# Schem_Motherboard.net
KiCad netlist of a schematic drawn in Altium Designer
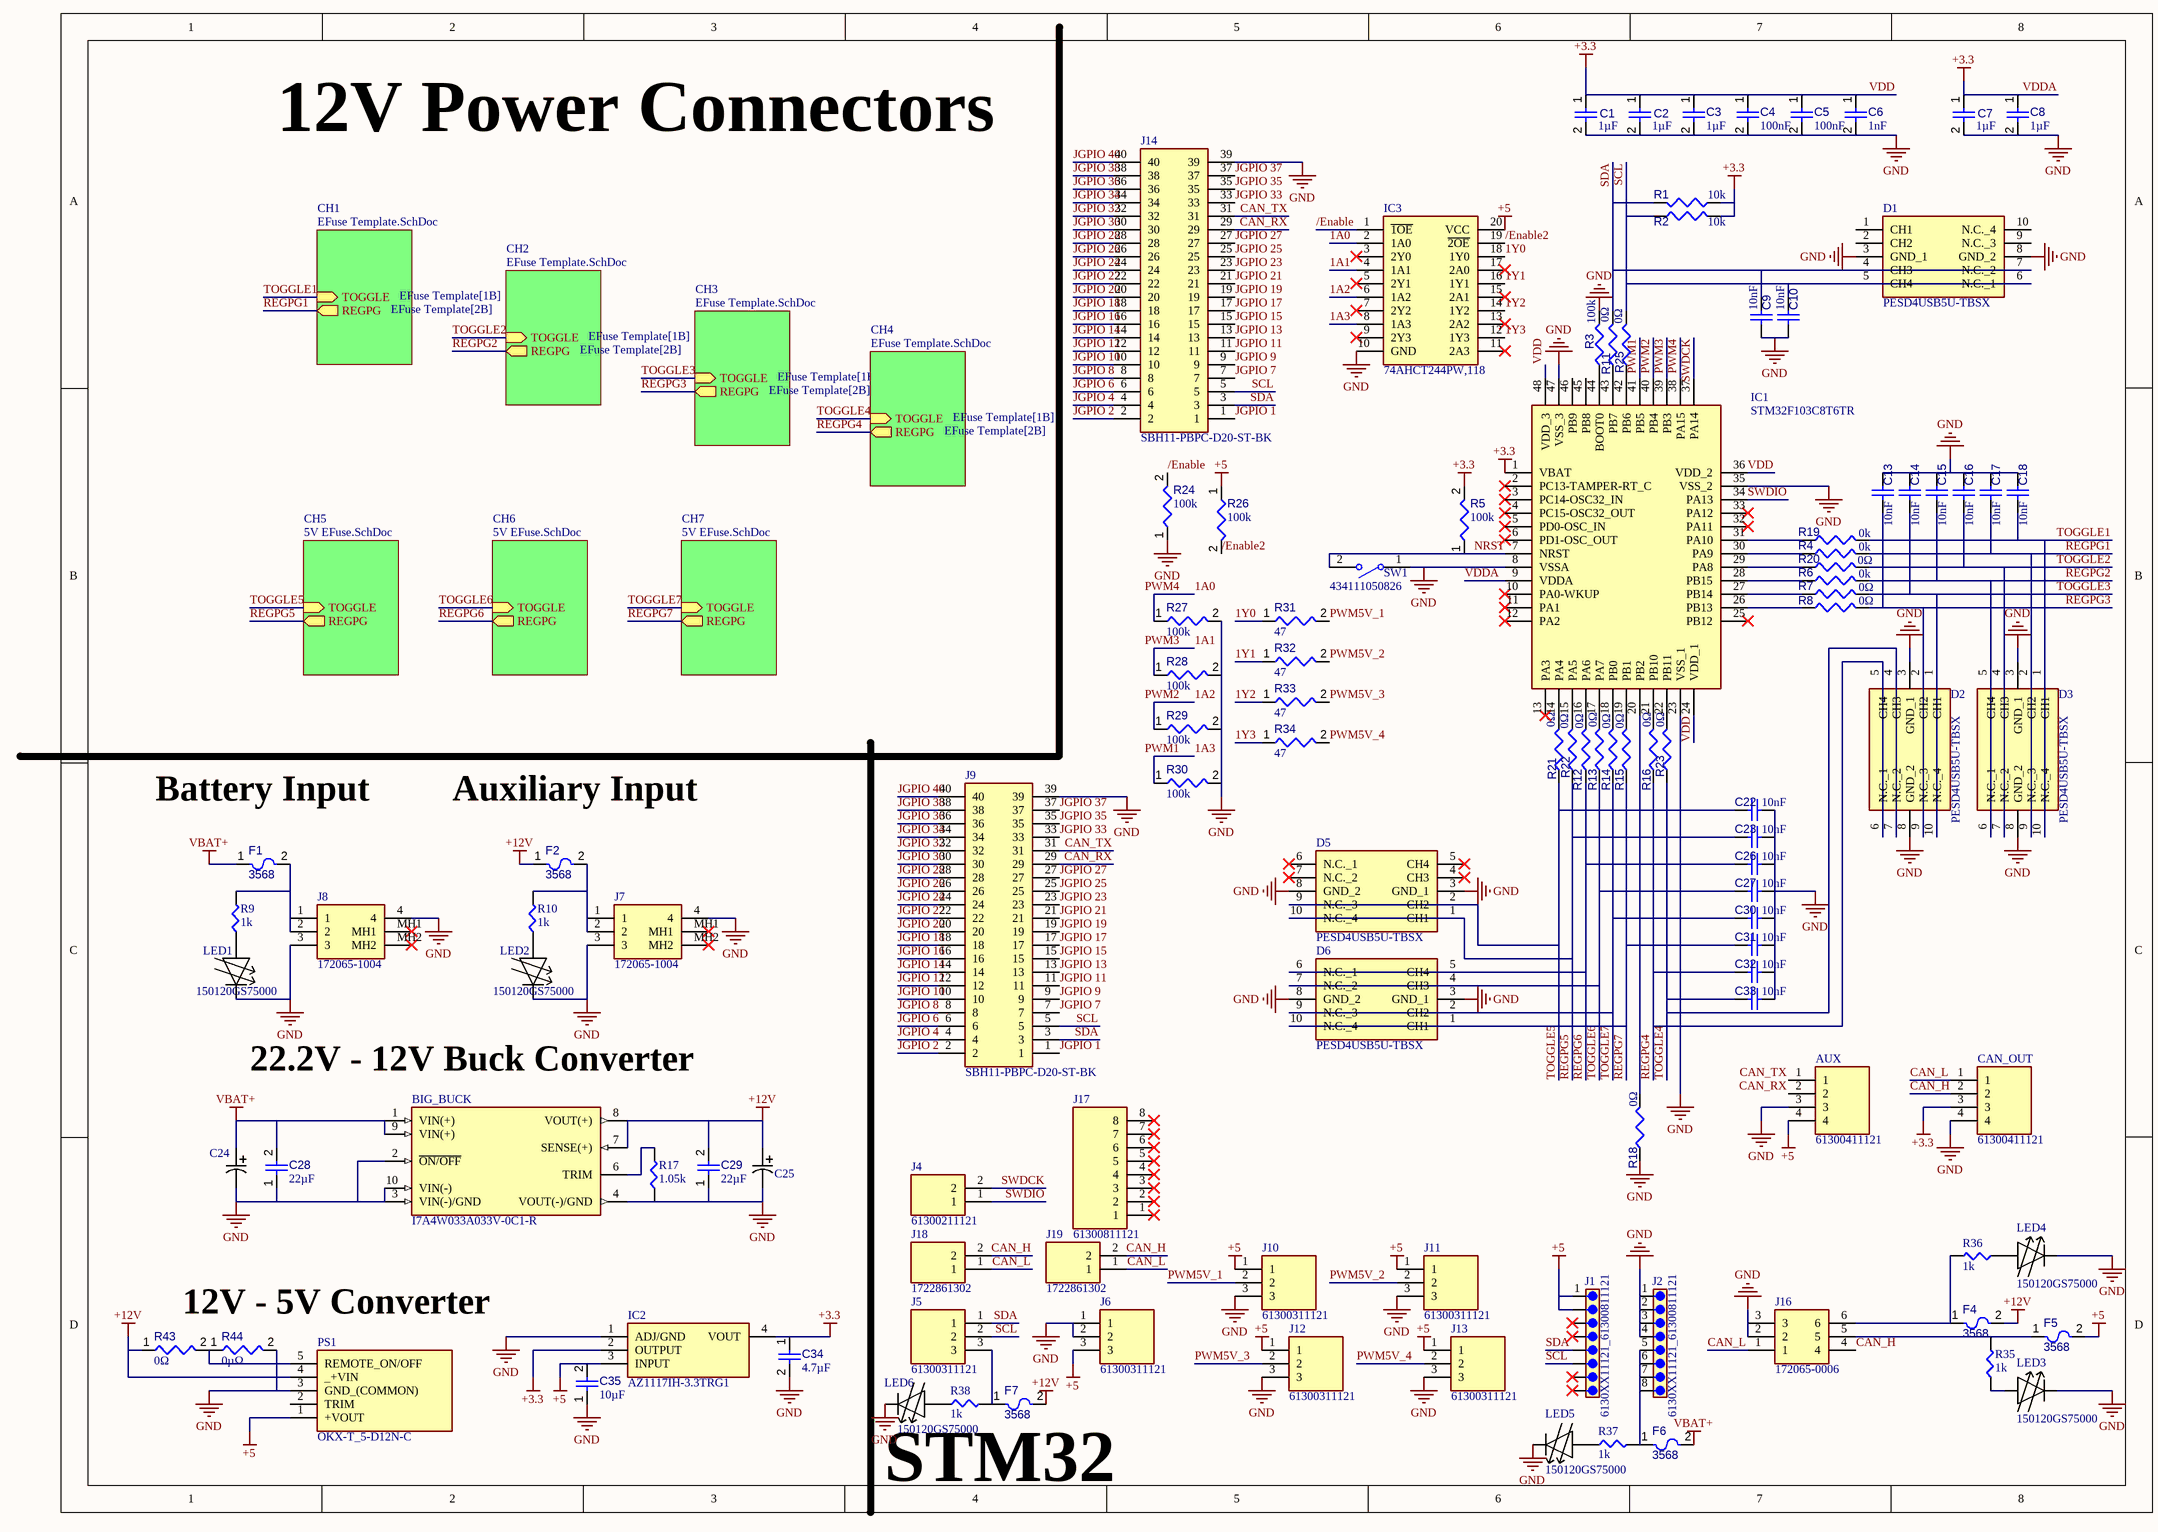
[diagram p0: Schem Motherboard.SchDoc]

(export (version "E")
  (design (tool "Eeschema 10.0.6"))
  (components
    (comp (ref "AUX")
      (value "61300411121")
      (footprint "SamacSys:HDRV4W95P0X254_1X4_1016X254X854P")
      (description "Connector")
      (fields (field (name "MOUSER PART NUMBER") "710-61300411121"))
      (libsource (lib "*") (part "61300411121"))
    )
    (comp (ref "BIG_BUCK")
      (value "I7A4W033A033V-0C1-R")
      (footprint "CONV_I7A4W033A033V-0C1-R")
      (description "Non-Isolated PoL Module DC DC Converter 1 Output 3.3V ~ 24V - - - 33A 18V - 60V Input")
      (fields (field (name "MF") "TDK-Lambda Americas Inc"))
      (libsource (lib "CPRT Workspace") (part "I7A4W033A033V-0C1-R"))
    )
    (comp (ref "C1")
      (value "1µF")
      (footprint "CAPC1608X94X35NL15T15")
      (description "Chip Capacitor, 1 uF, +/- 10%, 16 V, 0603 (1608 Metric)")
      (fields (field (name "TOLERANCE") "10%") (field (name "Comment") "Capacitor 1 uF +/- 10% 16 V 0603"))
      (libsource (lib "CPRT Workspace") (part "CAP-NP-2"))
    )
    (comp (ref "C2")
      (value "1µF")
      (footprint "CAPC1608X94X35NL15T15")
      (description "Chip Capacitor, 1 uF, +/- 10%, 16 V, 0603 (1608 Metric)")
      (fields (field (name "TOLERANCE") "10%") (field (name "Comment") "Capacitor 1 uF +/- 10% 16 V 0603"))
      (libsource (lib "CPRT Workspace") (part "CAP-NP-2"))
    )
    (comp (ref "C3")
      (value "1µF")
      (footprint "CAPC1608X94X35NL15T15")
      (description "Chip Capacitor, 1 uF, +/- 10%, 16 V, 0603 (1608 Metric)")
      (fields (field (name "TOLERANCE") "10%") (field (name "Comment") "Capacitor 1 uF +/- 10% 16 V 0603"))
      (libsource (lib "CPRT Workspace") (part "CAP-NP-2"))
    )
    (comp (ref "C4")
      (value "100nF")
      (footprint "CAPC1608X94X35NL15T15")
      (description "Chip Capacitor, 1 uF, +/- 10%, 16 V, 0603 (1608 Metric)")
      (fields (field (name "TOLERANCE") "10%") (field (name "Comment") "Capacitor 1 uF +/- 10% 16 V 0603"))
      (libsource (lib "CPRT Workspace") (part "CAP-NP-2"))
    )
    (comp (ref "C5")
      (value "100nF")
      (footprint "CAPC1608X94X35NL15T15")
      (description "Chip Capacitor, 1 uF, +/- 10%, 16 V, 0603 (1608 Metric)")
      (fields (field (name "TOLERANCE") "10%") (field (name "Comment") "Capacitor 1 uF +/- 10% 16 V 0603"))
      (libsource (lib "CPRT Workspace") (part "CAP-NP-2"))
    )
    (comp (ref "C6")
      (value "1nF")
      (footprint "CAPC1608X94X35NL15T15")
      (description "Chip Capacitor, 1 uF, +/- 10%, 16 V, 0603 (1608 Metric)")
      (fields (field (name "TOLERANCE") "10%") (field (name "Comment") "Capacitor 1 uF +/- 10% 16 V 0603"))
      (libsource (lib "CPRT Workspace") (part "CAP-NP-2"))
    )
    (comp (ref "C7")
      (value "1µF")
      (footprint "CAPC1608X94X35NL15T15")
      (description "Chip Capacitor, 1 uF, +/- 10%, 16 V, 0603 (1608 Metric)")
      (fields (field (name "TOLERANCE") "10%") (field (name "Comment") "Capacitor 1 uF +/- 10% 16 V 0603"))
      (libsource (lib "CPRT Workspace") (part "CAP-NP-2"))
    )
    (comp (ref "C8")
      (value "1µF")
      (footprint "CAPC1608X94X35NL15T15")
      (description "Chip Capacitor, 1 uF, +/- 10%, 16 V, 0603 (1608 Metric)")
      (fields (field (name "TOLERANCE") "10%") (field (name "Comment") "Capacitor 1 uF +/- 10% 16 V 0603"))
      (libsource (lib "CPRT Workspace") (part "CAP-NP-2"))
    )
    (comp (ref "C9")
      (value "10nF")
      (footprint "CAPC0402(1005)60_L")
      (description "Chip Capacitor, 10nF +/-20%, 50V, 0402, Thickness 0.6 mm")
      (fields (field (name "TOLERANCE") "5%") (field (name "Comment") "Capacitor 10nF +/-20% 50V 0402"))
      (libsource (lib "") (part "CAP-NP-2_1"))
    )
    (comp (ref "C10")
      (value "10nF")
      (footprint "CAPC0402(1005)60_L")
      (description "Chip Capacitor, 10nF +/-20%, 50V, 0402, Thickness 0.6 mm")
      (fields (field (name "TOLERANCE") "5%") (field (name "Comment") "Capacitor 10nF +/-20% 50V 0402"))
      (libsource (lib "") (part "CAP-NP-2_1"))
    )
    (comp (ref "C13")
      (value "10nF")
      (footprint "CAPC0402(1005)60_L")
      (description "Chip Capacitor, 10nF +/-20%, 50V, 0402, Thickness 0.6 mm")
      (fields (field (name "TOLERANCE") "5%") (field (name "Comment") "Capacitor 10nF +/-20% 50V 0402"))
      (libsource (lib "") (part "CAP-NP-2_1"))
    )
    (comp (ref "C14")
      (value "10nF")
      (footprint "CAPC0402(1005)60_L")
      (description "Chip Capacitor, 10nF +/-20%, 50V, 0402, Thickness 0.6 mm")
      (fields (field (name "TOLERANCE") "5%") (field (name "Comment") "Capacitor 10nF +/-20% 50V 0402"))
      (libsource (lib "") (part "CAP-NP-2_1"))
    )
    (comp (ref "C15")
      (value "10nF")
      (footprint "CAPC0402(1005)60_L")
      (description "Chip Capacitor, 10nF +/-20%, 50V, 0402, Thickness 0.6 mm")
      (fields (field (name "TOLERANCE") "5%") (field (name "Comment") "Capacitor 10nF +/-20% 50V 0402"))
      (libsource (lib "") (part "CAP-NP-2_1"))
    )
    (comp (ref "C16")
      (value "10nF")
      (footprint "CAPC0402(1005)60_L")
      (description "Chip Capacitor, 10nF +/-20%, 50V, 0402, Thickness 0.6 mm")
      (fields (field (name "TOLERANCE") "5%") (field (name "Comment") "Capacitor 10nF +/-20% 50V 0402"))
      (libsource (lib "") (part "CAP-NP-2_1"))
    )
    (comp (ref "C17")
      (value "10nF")
      (footprint "CAPC0402(1005)60_L")
      (description "Chip Capacitor, 10nF +/-20%, 50V, 0402, Thickness 0.6 mm")
      (fields (field (name "TOLERANCE") "5%") (field (name "Comment") "Capacitor 10nF +/-20% 50V 0402"))
      (libsource (lib "") (part "CAP-NP-2_1"))
    )
    (comp (ref "C18")
      (value "10nF")
      (footprint "CAPC0402(1005)60_L")
      (description "Chip Capacitor, 10nF +/-20%, 50V, 0402, Thickness 0.6 mm")
      (fields (field (name "TOLERANCE") "5%") (field (name "Comment") "Capacitor 10nF +/-20% 50V 0402"))
      (libsource (lib "") (part "CAP-NP-2_1"))
    )
    (comp (ref "C22")
      (value "10nF")
      (footprint "CAPC0402(1005)60_L")
      (description "Chip Capacitor, 10nF +/-20%, 50V, 0402, Thickness 0.6 mm")
      (fields (field (name "TOLERANCE") "5%") (field (name "Comment") "Capacitor 10nF +/-20% 50V 0402"))
      (libsource (lib "") (part "CAP-NP-2_1"))
    )
    (comp (ref "C23")
      (value "10nF")
      (footprint "CAPC0402(1005)60_L")
      (description "Chip Capacitor, 10nF +/-20%, 50V, 0402, Thickness 0.6 mm")
      (fields (field (name "TOLERANCE") "5%") (field (name "Comment") "Capacitor 10nF +/-20% 50V 0402"))
      (libsource (lib "") (part "CAP-NP-2_1"))
    )
    (comp (ref "C24")
      (value "UWT1E331MNL1GS")
      (footprint "PCAP_8x10-ELECT_NCA")
      (fields (field (name "COPYRIGHT") "Copyright (C) 2024 Ultra Librarian. All rights reserved."))
      (libsource (lib "CPRT Workspace") (part "UWT1E331MNL1GS"))
    )
    (comp (ref "C25")
      (value "UWT1E331MNL1GS")
      (footprint "PCAP_8x10-ELECT_NCA")
      (fields (field (name "COPYRIGHT") "Copyright (C) 2024 Ultra Librarian. All rights reserved."))
      (libsource (lib "CPRT Workspace") (part "UWT1E331MNL1GS"))
    )
    (comp (ref "C26")
      (value "10nF")
      (footprint "CAPC0402(1005)60_L")
      (description "Chip Capacitor, 10nF +/-20%, 50V, 0402, Thickness 0.6 mm")
      (fields (field (name "TOLERANCE") "5%") (field (name "Comment") "Capacitor 10nF +/-20% 50V 0402"))
      (libsource (lib "") (part "CAP-NP-2_1"))
    )
    (comp (ref "C27")
      (value "10nF")
      (footprint "CAPC0402(1005)60_L")
      (description "Chip Capacitor, 10nF +/-20%, 50V, 0402, Thickness 0.6 mm")
      (fields (field (name "TOLERANCE") "5%") (field (name "Comment") "Capacitor 10nF +/-20% 50V 0402"))
      (libsource (lib "") (part "CAP-NP-2_1"))
    )
    (comp (ref "C28")
      (value "22µF")
      (footprint "FP-GRM32E-0_3-0_2-IPC_C")
      (fields (field (name "Comment") "GRM32ER71E226ME15K"))
      (libsource (lib "CPRT Workspace") (part "CAP-NP-2"))
    )
    (comp (ref "C29")
      (value "22µF")
      (footprint "CAPC0805(2012)145_L")
      (description "Chip Capacitor, 22µF +/-40%, 16V, 0805, Thickness 1.45 mm")
      (fields (field (name "TOLERANCE") "5%") (field (name "Comment") "Capacitor 22µF +/-40% 16V 0805"))
      (libsource (lib "CPRT Workspace") (part "CAP-NP-2"))
    )
    (comp (ref "C30")
      (value "10nF")
      (footprint "CAPC0402(1005)60_L")
      (description "Chip Capacitor, 10nF +/-20%, 50V, 0402, Thickness 0.6 mm")
      (fields (field (name "TOLERANCE") "5%") (field (name "Comment") "Capacitor 10nF +/-20% 50V 0402"))
      (libsource (lib "") (part "CAP-NP-2_1"))
    )
    (comp (ref "C31")
      (value "10nF")
      (footprint "CAPC0402(1005)60_L")
      (description "Chip Capacitor, 10nF +/-20%, 50V, 0402, Thickness 0.6 mm")
      (fields (field (name "TOLERANCE") "5%") (field (name "Comment") "Capacitor 10nF +/-20% 50V 0402"))
      (libsource (lib "") (part "CAP-NP-2_1"))
    )
    (comp (ref "C32")
      (value "10nF")
      (footprint "CAPC0402(1005)60_L")
      (description "Chip Capacitor, 10nF +/-20%, 50V, 0402, Thickness 0.6 mm")
      (fields (field (name "TOLERANCE") "5%") (field (name "Comment") "Capacitor 10nF +/-20% 50V 0402"))
      (libsource (lib "") (part "CAP-NP-2_1"))
    )
    (comp (ref "C33")
      (value "10nF")
      (footprint "CAPC0402(1005)60_L")
      (description "Chip Capacitor, 10nF +/-20%, 50V, 0402, Thickness 0.6 mm")
      (fields (field (name "TOLERANCE") "5%") (field (name "Comment") "Capacitor 10nF +/-20% 50V 0402"))
      (libsource (lib "") (part "CAP-NP-2_1"))
    )
    (comp (ref "C34")
      (value "4.7µF")
      (footprint "CAPC0805(2012)145_L")
      (description "Chip Capacitor, 4.7µF +/-40%, 25V, 0805, Thickness 1.45 mm")
      (fields (field (name "TOLERANCE") "20%") (field (name "Comment") "Capacitor 4.7µF +/-40% 25V 0805"))
      (libsource (lib "CPRT Workspace") (part "CAP-NP-2"))
    )
    (comp (ref "C35")
      (value "10µF")
      (footprint "CAPC3216X180X50NL20T25")
      (description "Chip Capacitor, 10 uF, +/- 10%, 16 V, 1206 (3216 Metric)")
      (fields (field (name "TOLERANCE") "10%") (field (name "Comment") "Capacitor 10 uF +/- 10% 16 V 1206"))
      (libsource (lib "CPRT Workspace") (part "CAP-NP-2"))
    )
    (comp (ref "CAN_OUT")
      (value "61300411121")
      (footprint "SamacSys:HDRV4W95P0X254_1X4_1016X254X854P")
      (description "Connector")
      (fields (field (name "MOUSER PART NUMBER") "710-61300411121"))
      (libsource (lib "*") (part "61300411121"))
    )
    (comp (ref "D1")
      (value "PESD4USB5U-TBSX")
      (footprint "SamacSys:SON50P100X250X80-10N")
      (description "Diode")
      (fields (field (name "MOUSER PART NUMBER") "771-PESD4USB5U-TBSX"))
      (libsource (lib "*") (part "PESD4USB5U-TBSX"))
    )
    (comp (ref "D2")
      (value "PESD4USB5U-TBSX")
      (footprint "SamacSys:SON50P100X250X80-10N")
      (description "Diode")
      (fields (field (name "MOUSER PART NUMBER") "771-PESD4USB5U-TBSX"))
      (libsource (lib "") (part "PESD4USB5U-TBSX_1"))
    )
    (comp (ref "D3")
      (value "PESD4USB5U-TBSX")
      (footprint "SamacSys:SON50P100X250X80-10N")
      (description "Diode")
      (fields (field (name "MOUSER PART NUMBER") "771-PESD4USB5U-TBSX"))
      (libsource (lib "") (part "PESD4USB5U-TBSX_1"))
    )
    (comp (ref "D5")
      (value "PESD4USB5U-TBSX")
      (footprint "SamacSys:SON50P100X250X80-10N")
      (description "Diode")
      (fields (field (name "MOUSER PART NUMBER") "771-PESD4USB5U-TBSX"))
      (libsource (lib "") (part "PESD4USB5U-TBSX_2"))
    )
    (comp (ref "D6")
      (value "PESD4USB5U-TBSX")
      (footprint "SamacSys:SON50P100X250X80-10N")
      (description "Diode")
      (fields (field (name "MOUSER PART NUMBER") "771-PESD4USB5U-TBSX"))
      (libsource (lib "") (part "PESD4USB5U-TBSX_2"))
    )
    (comp (ref "F1")
      (value "3568")
      (footprint "KSTN-3568_V")
      (description "Fuses/Accessories")
      (libsource (lib "CPRT Workspace") (part "FUSE-2"))
    )
    (comp (ref "F2")
      (value "3568")
      (footprint "KSTN-3568_V")
      (description "Fuses/Accessories")
      (libsource (lib "CPRT Workspace") (part "FUSE-2"))
    )
    (comp (ref "F4")
      (value "3568")
      (footprint "KSTN-3568_V")
      (description "Fuses/Accessories")
      (libsource (lib "CPRT Workspace") (part "FUSE-2"))
    )
    (comp (ref "F5")
      (value "3568")
      (footprint "KSTN-3568_V")
      (description "Fuses/Accessories")
      (libsource (lib "CPRT Workspace") (part "FUSE-2"))
    )
    (comp (ref "F6")
      (value "3568")
      (footprint "KSTN-3568_V")
      (description "Fuses/Accessories")
      (libsource (lib "CPRT Workspace") (part "FUSE-2"))
    )
    (comp (ref "F7")
      (value "3568")
      (footprint "KSTN-3568_V")
      (description "Fuses/Accessories")
      (libsource (lib "CPRT Workspace") (part "FUSE-2"))
    )
    (comp (ref "IC1")
      (value "STM32F103C8T6TR")
      (footprint "SamacSys:QFP50P900X900X160-48N")
      (description "Integrated Circuit")
      (fields (field (name "MOUSER PART NUMBER") "511-STM32F103C8T6TR"))
      (libsource (lib "*") (part "STM32F103C8T6TR"))
    )
    (comp (ref "IC2")
      (value "AZ1117IH-3.3TRG1")
      (footprint "SamacSys:SOT230P700X180-4N")
      (description "Integrated Circuit")
      (fields (field (name "MOUSER PART NUMBER") "621-AZ1117IH-3.3TRG1"))
      (libsource (lib "*") (part "AZ1117IH-3.3TRG1"))
    )
    (comp (ref "IC3")
      (value "74AHCT244PW,118")
      (footprint "SamacSys:SOP65P640X110-20N")
      (description "Integrated Circuit")
      (fields (field (name "MOUSER PART NUMBER") "771-AHCT244PW118"))
      (libsource (lib "*") (part "74AHCT244PW,118"))
    )
    (comp (ref "J1")
      (value "6130XX11121_61300811121")
      (footprint "61300811121:61300811121")
      (fields (field (name "MF") "{'manufacturer': u'Wurth Electronics'}") (field (name "MP") "61300811121"))
      (libsource (lib "*") (part "6130XX11121_61300811121"))
    )
    (comp (ref "J2")
      (value "6130XX11121_61300811121")
      (footprint "61300811121:61300811121")
      (fields (field (name "MF") "{'manufacturer': u'Wurth Electronics'}") (field (name "MP") "61300811121"))
      (libsource (lib "*") (part "6130XX11121_61300811121"))
    )
    (comp (ref "J4")
      (value "61300211121")
      (footprint "SamacSys:HDRV2W110P0X254_1X2_508X254X854P")
      (description "Connector")
      (fields (field (name "MOUSER PART NUMBER") "710-61300211121"))
      (libsource (lib "*") (part "61300211121"))
    )
    (comp (ref "J5")
      (value "61300311121")
      (footprint "SamacSys:HDRV3W64P0X254_1X3_762X254X869P")
      (description "Connector")
      (fields (field (name "MOUSER PART NUMBER") "710-61300311121"))
      (libsource (lib "*") (part "61300311121"))
    )
    (comp (ref "J6")
      (value "61300311121")
      (footprint "SamacSys:HDRV3W64P0X254_1X3_762X254X869P")
      (description "Connector")
      (fields (field (name "MOUSER PART NUMBER") "710-61300311121"))
      (libsource (lib "") (part "61300311121_1"))
    )
    (comp (ref "J7")
      (value "172065-1004")
      (footprint "SamacSys:1720651004")
      (description "Connector")
      (fields (field (name "MOUSER PART NUMBER") "538-172065-1004"))
      (libsource (lib "*") (part "172065-1004"))
    )
    (comp (ref "J8")
      (value "172065-1004")
      (footprint "SamacSys:1720651004")
      (description "Connector")
      (fields (field (name "MOUSER PART NUMBER") "538-172065-1004"))
      (libsource (lib "*") (part "172065-1004"))
    )
    (comp (ref "J9")
      (value "SBH11-PBPC-D20-ST-BK")
      (footprint "SamacSys:SHDR40W64P254_2X20_5830X910X910P")
      (description "Connector")
      (libsource (lib "*") (part "SBH11-PBPC-D20-ST-BK"))
    )
    (comp (ref "J10")
      (value "61300311121")
      (footprint "HDRV3W64P0X254_1X3_762X254X869P")
      (description "WR-PHD 2.54 mm Pin Header 3 pins")
      (fields (field (name "MOUSER PART NUMBER") "710-61300311121"))
      (libsource (lib "CPRT Workspace") (part "61300311121"))
    )
    (comp (ref "J11")
      (value "61300311121")
      (footprint "HDRV3W64P0X254_1X3_762X254X869P")
      (description "WR-PHD 2.54 mm Pin Header 3 pins")
      (fields (field (name "MOUSER PART NUMBER") "710-61300311121"))
      (libsource (lib "CPRT Workspace") (part "61300311121"))
    )
    (comp (ref "J12")
      (value "61300311121")
      (footprint "HDRV3W64P0X254_1X3_762X254X869P")
      (description "WR-PHD 2.54 mm Pin Header 3 pins")
      (fields (field (name "MOUSER PART NUMBER") "710-61300311121"))
      (libsource (lib "CPRT Workspace") (part "61300311121"))
    )
    (comp (ref "J13")
      (value "61300311121")
      (footprint "HDRV3W64P0X254_1X3_762X254X869P")
      (description "WR-PHD 2.54 mm Pin Header 3 pins")
      (fields (field (name "MOUSER PART NUMBER") "710-61300311121"))
      (libsource (lib "CPRT Workspace") (part "61300311121"))
    )
    (comp (ref "J14")
      (value "SBH11-PBPC-D20-ST-BK")
      (footprint "SamacSys:SHDR40W64P254_2X20_5830X910X910P")
      (description "Connector")
      (libsource (lib "*") (part "SBH11-PBPC-D20-ST-BK"))
    )
    (comp (ref "J16")
      (value "172065-0006")
      (footprint "SamacSys:1720650006")
      (description "Connector")
      (fields (field (name "MOUSER PART NUMBER") "538-172065-0006"))
      (libsource (lib "*") (part "172065-0006"))
    )
    (comp (ref "J17")
      (value "61300811121")
      (footprint "SamacSys:HDRV8W64P0X254_1X8_2032X254X854P")
      (description "Connector")
      (fields (field (name "MOUSER PART NUMBER") "710-61300811121"))
      (libsource (lib "*") (part "61300811121"))
    )
    (comp (ref "J18")
      (value "1722861302")
      (footprint "SamacSys:1722861302")
      (description "Connector")
      (libsource (lib "*") (part "1722861302"))
    )
    (comp (ref "J19")
      (value "1722861302")
      (footprint "SamacSys:1722861302")
      (description "Connector")
      (libsource (lib "*") (part "1722861302"))
    )
    (comp (ref "LED1")
      (value "150120GS75000")
      (footprint "150120GS75000")
      (description "Green Status LED 1206")
      (libsource (lib "CPRT Workspace") (part "150120GS75000"))
    )
    (comp (ref "LED2")
      (value "150120GS75000")
      (footprint "150120GS75000")
      (description "Green Status LED 1206")
      (libsource (lib "CPRT Workspace") (part "150120GS75000"))
    )
    (comp (ref "LED3")
      (value "150120GS75000")
      (footprint "150120GS75000")
      (description "Green Status LED 1206")
      (libsource (lib "CPRT Workspace") (part "150120GS75000"))
    )
    (comp (ref "LED4")
      (value "150120GS75000")
      (footprint "150120GS75000")
      (description "Green Status LED 1206")
      (libsource (lib "CPRT Workspace") (part "150120GS75000"))
    )
    (comp (ref "LED5")
      (value "150120GS75000")
      (footprint "150120GS75000")
      (description "Green Status LED 1206")
      (libsource (lib "CPRT Workspace") (part "150120GS75000"))
    )
    (comp (ref "LED6")
      (value "150120GS75000")
      (footprint "150120GS75000")
      (description "Green Status LED 1206")
      (libsource (lib "CPRT Workspace") (part "150120GS75000"))
    )
    (comp (ref "PS1")
      (value "OKX-T_5-D12N-C")
      (footprint "SamacSys:OKXT5D12NC")
      (description "Power Supply")
      (fields
        (field (name "MANUFACTURER_PART_NUMBER") "OKX-T/5-D12N-C")
        (field (name "MOUSER PART NUMBER") "580-OKX-T/5-D12N-C")
      )
      (libsource (lib "*") (part "OKX-T_5-D12N-C"))
    )
    (comp (ref "R1")
      (value "10k")
      (footprint "RESC1608X55X25ML10T15")
      (description "Chip Resistor, 100 KOhm, +/- 1%, 0.1 W, -55 to 155 degC, 0603 (1608 Metric)")
      (fields (field (name "TOLERANCE") "1%") (field (name "POWER") "100mW"))
      (libsource (lib "CPRT Workspace") (part "RES-2"))
    )
    (comp (ref "R2")
      (value "10k")
      (footprint "RESC1608X55X25ML10T15")
      (description "Chip Resistor, 100 KOhm, +/- 1%, 0.1 W, -55 to 155 degC, 0603 (1608 Metric)")
      (fields (field (name "TOLERANCE") "1%") (field (name "POWER") "100mW"))
      (libsource (lib "CPRT Workspace") (part "RES-2"))
    )
    (comp (ref "R3")
      (value "100k")
      (footprint "RESC1608X55X25ML10T15")
      (description "Chip Resistor, 100 KOhm, +/- 1%, 0.1 W, -55 to 155 degC, 0603 (1608 Metric)")
      (fields (field (name "TOLERANCE") "1%") (field (name "POWER") "100mW"))
      (libsource (lib "CPRT Workspace") (part "RES-2"))
    )
    (comp (ref "R4")
      (value "0k")
      (footprint "RESC0402(1005)_L")
      (description "1K 0.063W 5% 0402 (1005 Metric)  SMD")
      (fields (field (name "POWER") "63mW") (field (name "TOLERANCE") "5%"))
      (libsource (lib "CPRT Workspace") (part "1KR2J"))
    )
    (comp (ref "R5")
      (value "100k")
      (footprint "RESC1608X55X25ML10T15")
      (description "Chip Resistor, 100 KOhm, +/- 1%, 0.1 W, -55 to 155 degC, 0603 (1608 Metric)")
      (fields (field (name "TOLERANCE") "1%") (field (name "POWER") "100mW"))
      (libsource (lib "") (part "RES-2_1"))
    )
    (comp (ref "R6")
      (value "0k")
      (footprint "RESC0402(1005)_L")
      (description "1K 0.063W 5% 0402 (1005 Metric)  SMD")
      (fields (field (name "POWER") "63mW") (field (name "TOLERANCE") "5%"))
      (libsource (lib "CPRT Workspace") (part "1KR2J"))
    )
    (comp (ref "R7")
      (value "0Ω")
      (footprint "RESC0402(1005)_L")
      (description "1K 0.063W 5% 0402 (1005 Metric)  SMD")
      (fields (field (name "POWER") "63mW") (field (name "TOLERANCE") "5%"))
      (libsource (lib "CPRT Workspace") (part "1KR2J"))
    )
    (comp (ref "R8")
      (value "0Ω")
      (footprint "RESC0402(1005)_L")
      (description "1K 0.063W 5% 0402 (1005 Metric)  SMD")
      (fields (field (name "POWER") "63mW") (field (name "TOLERANCE") "5%"))
      (libsource (lib "CPRT Workspace") (part "1KR2J"))
    )
    (comp (ref "R9")
      (value "1k")
      (footprint "SMD-1206-RES")
      (description "RES SMD 1K OHM 5% 2/3W 1206")
      (fields
        (field (name "DIGI-KEY PART NUMBER") "P1.0KALCT-ND")
        (field (name "PART NUMBER") "ERJ-P08J102V")
      )
      (libsource (lib "CPRT Workspace") (part "Symbol"))
    )
    (comp (ref "R10")
      (value "1k")
      (footprint "SMD-1206-RES")
      (description "RES SMD 1K OHM 5% 2/3W 1206")
      (fields
        (field (name "DIGI-KEY PART NUMBER") "P1.0KALCT-ND")
        (field (name "PART NUMBER") "ERJ-P08J102V")
      )
      (libsource (lib "CPRT Workspace") (part "Symbol"))
    )
    (comp (ref "R11")
      (value "0Ω")
      (footprint "RESC0402(1005)_L")
      (description "1K 0.063W 5% 0402 (1005 Metric)  SMD")
      (fields (field (name "POWER") "63mW") (field (name "TOLERANCE") "5%"))
      (libsource (lib "CPRT Workspace") (part "1KR2J"))
    )
    (comp (ref "R12")
      (value "0Ω")
      (footprint "RESC0402(1005)_L")
      (description "1K 0.063W 5% 0402 (1005 Metric)  SMD")
      (fields (field (name "POWER") "63mW") (field (name "TOLERANCE") "5%"))
      (libsource (lib "CPRT Workspace") (part "1KR2J"))
    )
    (comp (ref "R13")
      (value "0Ω")
      (footprint "RESC0402(1005)_L")
      (description "1K 0.063W 5% 0402 (1005 Metric)  SMD")
      (fields (field (name "POWER") "63mW") (field (name "TOLERANCE") "5%"))
      (libsource (lib "CPRT Workspace") (part "1KR2J"))
    )
    (comp (ref "R14")
      (value "0Ω")
      (footprint "RESC0402(1005)_L")
      (description "1K 0.063W 5% 0402 (1005 Metric)  SMD")
      (fields (field (name "POWER") "63mW") (field (name "TOLERANCE") "5%"))
      (libsource (lib "CPRT Workspace") (part "1KR2J"))
    )
    (comp (ref "R15")
      (value "0Ω")
      (footprint "RESC0402(1005)_L")
      (description "1K 0.063W 5% 0402 (1005 Metric)  SMD")
      (fields (field (name "POWER") "63mW") (field (name "TOLERANCE") "5%"))
      (libsource (lib "CPRT Workspace") (part "1KR2J"))
    )
    (comp (ref "R16")
      (value "0Ω")
      (footprint "RESC0402(1005)_L")
      (description "1K 0.063W 5% 0402 (1005 Metric)  SMD")
      (fields (field (name "POWER") "63mW") (field (name "TOLERANCE") "5%"))
      (libsource (lib "CPRT Workspace") (part "1KR2J"))
    )
    (comp (ref "R17")
      (value "1.05k")
      (footprint "SMD-1206-RES")
      (description "RES SMD 1.05K OHM 1% 1/4W 1206")
      (fields
        (field (name "TOLERANCE") "±1%")
        (field (name "MANUFACTURER") "Panasonic Electronic Components")
      )
      (libsource (lib "CPRT Workspace") (part "Symbol"))
    )
    (comp (ref "R18")
      (value "0Ω")
      (footprint "RESC0402(1005)_L")
      (description "1K 0.063W 5% 0402 (1005 Metric)  SMD")
      (fields (field (name "POWER") "63mW") (field (name "TOLERANCE") "5%"))
      (libsource (lib "CPRT Workspace") (part "1KR2J"))
    )
    (comp (ref "R19")
      (value "0k")
      (footprint "RESC0402(1005)_L")
      (description "1K 0.063W 5% 0402 (1005 Metric)  SMD")
      (fields (field (name "POWER") "63mW") (field (name "TOLERANCE") "5%"))
      (libsource (lib "CPRT Workspace") (part "1KR2J"))
    )
    (comp (ref "R20")
      (value "0Ω")
      (footprint "RESC0402(1005)_L")
      (description "1K 0.063W 5% 0402 (1005 Metric)  SMD")
      (fields (field (name "POWER") "63mW") (field (name "TOLERANCE") "5%"))
      (libsource (lib "CPRT Workspace") (part "1KR2J"))
    )
    (comp (ref "R21")
      (value "0Ω")
      (footprint "RESC0402(1005)_L")
      (description "1K 0.063W 5% 0402 (1005 Metric)  SMD")
      (fields (field (name "POWER") "63mW") (field (name "TOLERANCE") "5%"))
      (libsource (lib "CPRT Workspace") (part "1KR2J"))
    )
    (comp (ref "R22")
      (value "0Ω")
      (footprint "RESC0402(1005)_L")
      (description "1K 0.063W 5% 0402 (1005 Metric)  SMD")
      (fields (field (name "POWER") "63mW") (field (name "TOLERANCE") "5%"))
      (libsource (lib "CPRT Workspace") (part "1KR2J"))
    )
    (comp (ref "R23")
      (value "0Ω")
      (footprint "RESC0402(1005)_L")
      (description "1K 0.063W 5% 0402 (1005 Metric)  SMD")
      (fields (field (name "POWER") "63mW") (field (name "TOLERANCE") "5%"))
      (libsource (lib "CPRT Workspace") (part "1KR2J"))
    )
    (comp (ref "R24")
      (value "100k")
      (footprint "RESC1608X55X25ML10T15")
      (description "Chip Resistor, 100 KOhm, +/- 1%, 0.1 W, -55 to 155 degC, 0603 (1608 Metric)")
      (fields (field (name "TOLERANCE") "1%") (field (name "POWER") "100mW"))
      (libsource (lib "") (part "RES-2_1"))
    )
    (comp (ref "R25")
      (value "0Ω")
      (footprint "RESC0402(1005)_L")
      (description "1K 0.063W 5% 0402 (1005 Metric)  SMD")
      (fields (field (name "POWER") "63mW") (field (name "TOLERANCE") "5%"))
      (libsource (lib "CPRT Workspace") (part "1KR2J"))
    )
    (comp (ref "R26")
      (value "100k")
      (footprint "RESC1608X55X25ML10T15")
      (description "Chip Resistor, 100 KOhm, +/- 1%, 0.1 W, -55 to 155 degC, 0603 (1608 Metric)")
      (fields (field (name "TOLERANCE") "1%") (field (name "POWER") "100mW"))
      (libsource (lib "") (part "RES-2_1"))
    )
    (comp (ref "R27")
      (value "100k")
      (footprint "RESC1608X55X25ML10T15")
      (description "Chip Resistor, 100 KOhm, +/- 1%, 0.1 W, -55 to 155 degC, 0603 (1608 Metric)")
      (fields (field (name "TOLERANCE") "1%") (field (name "POWER") "100mW"))
      (libsource (lib "") (part "RES-2_1"))
    )
    (comp (ref "R28")
      (value "100k")
      (footprint "RESC1608X55X25ML10T15")
      (description "Chip Resistor, 100 KOhm, +/- 1%, 0.1 W, -55 to 155 degC, 0603 (1608 Metric)")
      (fields (field (name "TOLERANCE") "1%") (field (name "POWER") "100mW"))
      (libsource (lib "") (part "RES-2_1"))
    )
    (comp (ref "R29")
      (value "100k")
      (footprint "RESC1608X55X25ML10T15")
      (description "Chip Resistor, 100 KOhm, +/- 1%, 0.1 W, -55 to 155 degC, 0603 (1608 Metric)")
      (fields (field (name "TOLERANCE") "1%") (field (name "POWER") "100mW"))
      (libsource (lib "") (part "RES-2_1"))
    )
    (comp (ref "R30")
      (value "100k")
      (footprint "RESC1608X55X25ML10T15")
      (description "Chip Resistor, 100 KOhm, +/- 1%, 0.1 W, -55 to 155 degC, 0603 (1608 Metric)")
      (fields (field (name "TOLERANCE") "1%") (field (name "POWER") "100mW"))
      (libsource (lib "") (part "RES-2_1"))
    )
    (comp (ref "R31")
      (value "47")
      (footprint "RESC1608X55X25ML10T15")
      (description "Chip Resistor, 100 KOhm, +/- 1%, 0.1 W, -55 to 155 degC, 0603 (1608 Metric)")
      (fields (field (name "TOLERANCE") "1%") (field (name "POWER") "100mW"))
      (libsource (lib "") (part "RES-2_1"))
    )
    (comp (ref "R32")
      (value "47")
      (footprint "RESC1608X55X25ML10T15")
      (description "Chip Resistor, 100 KOhm, +/- 1%, 0.1 W, -55 to 155 degC, 0603 (1608 Metric)")
      (fields (field (name "TOLERANCE") "1%") (field (name "POWER") "100mW"))
      (libsource (lib "") (part "RES-2_1"))
    )
    (comp (ref "R33")
      (value "47")
      (footprint "RESC1608X55X25ML10T15")
      (description "Chip Resistor, 100 KOhm, +/- 1%, 0.1 W, -55 to 155 degC, 0603 (1608 Metric)")
      (fields (field (name "TOLERANCE") "1%") (field (name "POWER") "100mW"))
      (libsource (lib "") (part "RES-2_1"))
    )
    (comp (ref "R34")
      (value "47")
      (footprint "RESC1608X55X25ML10T15")
      (description "Chip Resistor, 100 KOhm, +/- 1%, 0.1 W, -55 to 155 degC, 0603 (1608 Metric)")
      (fields (field (name "TOLERANCE") "1%") (field (name "POWER") "100mW"))
      (libsource (lib "") (part "RES-2_1"))
    )
    (comp (ref "R35")
      (value "1k")
      (footprint "SMD-1206-RES")
      (description "RES SMD 1K OHM 5% 2/3W 1206")
      (fields
        (field (name "DIGI-KEY PART NUMBER") "P1.0KALCT-ND")
        (field (name "PART NUMBER") "ERJ-P08J102V")
      )
      (libsource (lib "CPRT Workspace") (part "Symbol"))
    )
    (comp (ref "R36")
      (value "1k")
      (footprint "SMD-1206-RES")
      (description "RES SMD 1K OHM 5% 2/3W 1206")
      (fields
        (field (name "DIGI-KEY PART NUMBER") "P1.0KALCT-ND")
        (field (name "PART NUMBER") "ERJ-P08J102V")
      )
      (libsource (lib "CPRT Workspace") (part "Symbol"))
    )
    (comp (ref "R37")
      (value "1k")
      (footprint "SMD-1206-RES")
      (description "RES SMD 1K OHM 5% 2/3W 1206")
      (fields
        (field (name "DIGI-KEY PART NUMBER") "P1.0KALCT-ND")
        (field (name "PART NUMBER") "ERJ-P08J102V")
      )
      (libsource (lib "CPRT Workspace") (part "Symbol"))
    )
    (comp (ref "R38")
      (value "1k")
      (footprint "SMD-1206-RES")
      (description "RES SMD 1K OHM 5% 2/3W 1206")
      (fields
        (field (name "DIGI-KEY PART NUMBER") "P1.0KALCT-ND")
        (field (name "PART NUMBER") "ERJ-P08J102V")
      )
      (libsource (lib "CPRT Workspace") (part "Symbol"))
    )
    (comp (ref "R43")
      (value "0Ω")
      (footprint "RESC0805(2012)_L")
      (description "1K 0.125W 5% 0805 (2012 Metric)  SMD")
      (fields (field (name "TOLERANCE") "5%") (field (name "POWER") "125mW"))
      (libsource (lib "CPRT Workspace") (part "1KR5J"))
    )
    (comp (ref "R44")
      (value "0µΩ")
      (footprint "RESC0805(2012)_L")
      (description "1K 0.125W 5% 0805 (2012 Metric)  SMD")
      (fields (field (name "TOLERANCE") "5%") (field (name "POWER") "125mW"))
      (libsource (lib "CPRT Workspace") (part "1KR5J"))
    )
    (comp (ref "SW1")
      (value "434111050826")
      (footprint "434111050826")
      (libsource (lib "CPRT Workspace") (part "SPST-NO_2P"))
    )
  )
  (nets
    (net (code "1") (name "+3.3") (class "Default")
      (node (ref "C1") (pin "1") (pinfunction "1_1") (pintype "passive"))
      (node (ref "C2") (pin "1") (pinfunction "1_1") (pintype "passive"))
      (node (ref "C3") (pin "1") (pinfunction "1_1") (pintype "passive"))
      (node (ref "C34") (pin "1") (pinfunction "1_1") (pintype "passive"))
      (node (ref "C4") (pin "1") (pinfunction "1_1") (pintype "passive"))
      (node (ref "C5") (pin "1") (pinfunction "1_1") (pintype "passive"))
      (node (ref "C6") (pin "1") (pinfunction "1_1") (pintype "passive"))
      (node (ref "C7") (pin "1") (pinfunction "1_1") (pintype "passive"))
      (node (ref "C8") (pin "1") (pinfunction "1_1") (pintype "passive"))
      (node (ref "CAN_OUT") (pin "3") (pinfunction "3_3") (pintype "passive"))
      (node (ref "IC1") (pin "1") (pinfunction "VBAT_1") (pintype "passive"))
      (node (ref "IC1") (pin "24") (pinfunction "VDD_1_24") (pintype "passive"))
      (node (ref "IC1") (pin "36") (pinfunction "VDD_2_36") (pintype "passive"))
      (node (ref "IC1") (pin "48") (pinfunction "VDD_3_48") (pintype "passive"))
      (node (ref "IC1") (pin "9") (pinfunction "VDDA_9") (pintype "passive"))
      (node (ref "IC2") (pin "2") (pinfunction "OUTPUT_2") (pintype "passive"))
      (node (ref "IC2") (pin "4") (pinfunction "VOUT_4") (pintype "passive"))
      (node (ref "R1") (pin "1") (pinfunction "1_1") (pintype "passive"))
      (node (ref "R2") (pin "2") (pinfunction "2_2") (pintype "passive"))
      (node (ref "R5") (pin "2") (pinfunction "2_2") (pintype "passive"))
    )
    (net (code "2") (name "+5") (class "Default")
      (node (ref "AUX") (pin "4") (pinfunction "4_4") (pintype "passive"))
      (node (ref "C35") (pin "2") (pinfunction "2_2") (pintype "passive"))
      (node (ref "F5") (pin "2") (pinfunction "2_2") (pintype "passive"))
      (node (ref "IC2") (pin "3") (pinfunction "INPUT_3") (pintype "passive"))
      (node (ref "IC3") (pin "20") (pinfunction "VCC_20") (pintype "passive"))
      (node (ref "J1") (pin "1") (pinfunction "1_1") (pintype "passive"))
      (node (ref "J1") (pin "2") (pinfunction "2_2") (pintype "passive"))
      (node (ref "J10") (pin "1") (pinfunction "1_1") (pintype "passive"))
      (node (ref "J11") (pin "1") (pinfunction "1_1") (pintype "passive"))
      (node (ref "J12") (pin "1") (pinfunction "1_1") (pintype "passive"))
      (node (ref "J13") (pin "1") (pinfunction "1_1") (pintype "passive"))
      (node (ref "J6") (pin "3") (pinfunction "3_3") (pintype "passive"))
      (node (ref "PS1") (pin "1") (pinfunction "+VOUT_1") (pintype "passive"))
      (node (ref "R26") (pin "1") (pinfunction "1_1") (pintype "passive"))
    )
    (net (code "3") (name "+12V") (class "Default")
      (node (ref "BIG_BUCK") (pin "7") (pinfunction "SENSE(+)_7") (pintype "input"))
      (node (ref "BIG_BUCK") (pin "8") (pinfunction "VOUT(+)_8") (pintype "output"))
      (node (ref "C25") (pin "1") (pinfunction "1_1") (pintype "passive"))
      (node (ref "C29") (pin "2") (pinfunction "2_2") (pintype "passive"))
      (node (ref "F2") (pin "1") (pinfunction "1_1") (pintype "passive"))
      (node (ref "F4") (pin "2") (pinfunction "2_2") (pintype "passive"))
      (node (ref "F7") (pin "2") (pinfunction "2_2") (pintype "passive"))
      (node (ref "PS1") (pin "4") (pinfunction "_+VIN_4") (pintype "passive"))
      (node (ref "R43") (pin "1") (pinfunction "1_1") (pintype "passive"))
    )
    (net (code "4") (name "/1A0") (class "Default")
      (node (ref "IC1") (pin "38") (pinfunction "PA15_38") (pintype "passive"))
      (node (ref "IC3") (pin "2") (pinfunction "1A0_2") (pintype "passive"))
      (node (ref "R27") (pin "1") (pinfunction "1_1") (pintype "passive"))
    )
    (net (code "5") (name "/1A1") (class "Default")
      (node (ref "IC1") (pin "39") (pinfunction "PB3_39") (pintype "passive"))
      (node (ref "IC3") (pin "4") (pinfunction "1A1_4") (pintype "passive"))
      (node (ref "R28") (pin "1") (pinfunction "1_1") (pintype "passive"))
    )
    (net (code "6") (name "/1A2") (class "Default")
      (node (ref "IC1") (pin "40") (pinfunction "PB4_40") (pintype "passive"))
      (node (ref "IC3") (pin "6") (pinfunction "1A2_6") (pintype "passive"))
      (node (ref "R29") (pin "1") (pinfunction "1_1") (pintype "passive"))
    )
    (net (code "7") (name "/1A3") (class "Default")
      (node (ref "IC1") (pin "41") (pinfunction "PB5_41") (pintype "passive"))
      (node (ref "IC3") (pin "8") (pinfunction "1A3_8") (pintype "passive"))
      (node (ref "R30") (pin "1") (pinfunction "1_1") (pintype "passive"))
    )
    (net (code "8") (name "/1Y0") (class "Default")
      (node (ref "IC3") (pin "18") (pinfunction "1Y0_18") (pintype "passive"))
      (node (ref "R31") (pin "1") (pinfunction "1_1") (pintype "passive"))
    )
    (net (code "9") (name "/1Y1") (class "Default")
      (node (ref "IC3") (pin "16") (pinfunction "1Y1_16") (pintype "passive"))
      (node (ref "R32") (pin "1") (pinfunction "1_1") (pintype "passive"))
    )
    (net (code "10") (name "/1Y2") (class "Default")
      (node (ref "IC3") (pin "14") (pinfunction "1Y2_14") (pintype "passive"))
      (node (ref "R33") (pin "1") (pinfunction "1_1") (pintype "passive"))
    )
    (net (code "11") (name "/1Y3") (class "Default")
      (node (ref "IC3") (pin "12") (pinfunction "1Y3_12") (pintype "passive"))
      (node (ref "R34") (pin "1") (pinfunction "1_1") (pintype "passive"))
    )
    (net (code "12") (name "/CAN_H") (class "Default")
      (node (ref "CAN_OUT") (pin "2") (pinfunction "2_2") (pintype "passive"))
      (node (ref "J16") (pin "4") (pinfunction "4_4") (pintype "passive"))
      (node (ref "J18") (pin "2") (pinfunction "2_2") (pintype "passive"))
      (node (ref "J19") (pin "2") (pinfunction "2_2") (pintype "passive"))
    )
    (net (code "13") (name "/CAN_L") (class "Default")
      (node (ref "CAN_OUT") (pin "1") (pinfunction "1_1") (pintype "passive"))
      (node (ref "J16") (pin "1") (pinfunction "1_1") (pintype "passive"))
      (node (ref "J18") (pin "1") (pinfunction "1_1") (pintype "passive"))
      (node (ref "J19") (pin "1") (pinfunction "1_1") (pintype "passive"))
    )
    (net (code "14") (name "/CAN_RX") (class "Default")
      (node (ref "AUX") (pin "2") (pinfunction "2_2") (pintype "passive"))
      (node (ref "J14") (pin "29") (pinfunction "29_29") (pintype "passive"))
      (node (ref "J9") (pin "29") (pinfunction "29_29") (pintype "passive"))
    )
    (net (code "15") (name "/CAN_TX") (class "Default")
      (node (ref "AUX") (pin "1") (pinfunction "1_1") (pintype "passive"))
      (node (ref "J14") (pin "31") (pinfunction "31_31") (pintype "passive"))
      (node (ref "J9") (pin "31") (pinfunction "31_31") (pintype "passive"))
    )
    (net (code "16") (name "/JGPIO 1") (class "Default")
      (node (ref "J14") (pin "1") (pinfunction "1_1") (pintype "passive"))
      (node (ref "J9") (pin "1") (pinfunction "1_1") (pintype "passive"))
    )
    (net (code "17") (name "/JGPIO 2") (class "Default")
      (node (ref "J14") (pin "2") (pinfunction "2_2") (pintype "passive"))
      (node (ref "J9") (pin "2") (pinfunction "2_2") (pintype "passive"))
    )
    (net (code "18") (name "/JGPIO 4") (class "Default")
      (node (ref "J14") (pin "4") (pinfunction "4_4") (pintype "passive"))
      (node (ref "J9") (pin "4") (pinfunction "4_4") (pintype "passive"))
    )
    (net (code "19") (name "/JGPIO 6") (class "Default")
      (node (ref "J14") (pin "6") (pinfunction "6_6") (pintype "passive"))
      (node (ref "J9") (pin "6") (pinfunction "6_6") (pintype "passive"))
    )
    (net (code "20") (name "/JGPIO 7") (class "Default")
      (node (ref "J14") (pin "7") (pinfunction "7_7") (pintype "passive"))
      (node (ref "J9") (pin "7") (pinfunction "7_7") (pintype "passive"))
    )
    (net (code "21") (name "/JGPIO 8") (class "Default")
      (node (ref "J14") (pin "8") (pinfunction "8_8") (pintype "passive"))
      (node (ref "J9") (pin "8") (pinfunction "8_8") (pintype "passive"))
    )
    (net (code "22") (name "/JGPIO 9") (class "Default")
      (node (ref "J14") (pin "9") (pinfunction "9_9") (pintype "passive"))
      (node (ref "J9") (pin "9") (pinfunction "9_9") (pintype "passive"))
    )
    (net (code "23") (name "/JGPIO 10") (class "Default")
      (node (ref "J14") (pin "10") (pinfunction "10_10") (pintype "passive"))
      (node (ref "J9") (pin "10") (pinfunction "10_10") (pintype "passive"))
    )
    (net (code "24") (name "/JGPIO 11") (class "Default")
      (node (ref "J14") (pin "11") (pinfunction "11_11") (pintype "passive"))
      (node (ref "J9") (pin "11") (pinfunction "11_11") (pintype "passive"))
    )
    (net (code "25") (name "/JGPIO 12") (class "Default")
      (node (ref "J14") (pin "12") (pinfunction "12_12") (pintype "passive"))
      (node (ref "J9") (pin "12") (pinfunction "12_12") (pintype "passive"))
    )
    (net (code "26") (name "/JGPIO 13") (class "Default")
      (node (ref "J14") (pin "13") (pinfunction "13_13") (pintype "passive"))
      (node (ref "J9") (pin "13") (pinfunction "13_13") (pintype "passive"))
    )
    (net (code "27") (name "/JGPIO 14") (class "Default")
      (node (ref "J14") (pin "14") (pinfunction "14_14") (pintype "passive"))
      (node (ref "J9") (pin "14") (pinfunction "14_14") (pintype "passive"))
    )
    (net (code "28") (name "/JGPIO 15") (class "Default")
      (node (ref "J14") (pin "15") (pinfunction "15_15") (pintype "passive"))
      (node (ref "J9") (pin "15") (pinfunction "15_15") (pintype "passive"))
    )
    (net (code "29") (name "/JGPIO 16") (class "Default")
      (node (ref "J14") (pin "16") (pinfunction "16_16") (pintype "passive"))
      (node (ref "J9") (pin "16") (pinfunction "16_16") (pintype "passive"))
    )
    (net (code "30") (name "/JGPIO 17") (class "Default")
      (node (ref "J14") (pin "17") (pinfunction "17_17") (pintype "passive"))
      (node (ref "J9") (pin "17") (pinfunction "17_17") (pintype "passive"))
    )
    (net (code "31") (name "/JGPIO 18") (class "Default")
      (node (ref "J14") (pin "18") (pinfunction "18_18") (pintype "passive"))
      (node (ref "J9") (pin "18") (pinfunction "18_18") (pintype "passive"))
    )
    (net (code "32") (name "/JGPIO 19") (class "Default")
      (node (ref "J14") (pin "19") (pinfunction "19_19") (pintype "passive"))
      (node (ref "J9") (pin "19") (pinfunction "19_19") (pintype "passive"))
    )
    (net (code "33") (name "/JGPIO 20") (class "Default")
      (node (ref "J14") (pin "20") (pinfunction "20_20") (pintype "passive"))
      (node (ref "J9") (pin "20") (pinfunction "20_20") (pintype "passive"))
    )
    (net (code "34") (name "/JGPIO 21") (class "Default")
      (node (ref "J14") (pin "21") (pinfunction "21_21") (pintype "passive"))
      (node (ref "J9") (pin "21") (pinfunction "21_21") (pintype "passive"))
    )
    (net (code "35") (name "/JGPIO 22") (class "Default")
      (node (ref "J14") (pin "22") (pinfunction "22_22") (pintype "passive"))
      (node (ref "J9") (pin "22") (pinfunction "22_22") (pintype "passive"))
    )
    (net (code "36") (name "/JGPIO 23") (class "Default")
      (node (ref "J14") (pin "23") (pinfunction "23_23") (pintype "passive"))
      (node (ref "J9") (pin "23") (pinfunction "23_23") (pintype "passive"))
    )
    (net (code "37") (name "/JGPIO 24") (class "Default")
      (node (ref "J14") (pin "24") (pinfunction "24_24") (pintype "passive"))
      (node (ref "J9") (pin "24") (pinfunction "24_24") (pintype "passive"))
    )
    (net (code "38") (name "/JGPIO 25") (class "Default")
      (node (ref "J14") (pin "25") (pinfunction "25_25") (pintype "passive"))
      (node (ref "J9") (pin "25") (pinfunction "25_25") (pintype "passive"))
    )
    (net (code "39") (name "/JGPIO 26") (class "Default")
      (node (ref "J14") (pin "26") (pinfunction "26_26") (pintype "passive"))
      (node (ref "J9") (pin "26") (pinfunction "26_26") (pintype "passive"))
    )
    (net (code "40") (name "/JGPIO 27") (class "Default")
      (node (ref "J14") (pin "27") (pinfunction "27_27") (pintype "passive"))
      (node (ref "J9") (pin "27") (pinfunction "27_27") (pintype "passive"))
    )
    (net (code "41") (name "/JGPIO 28") (class "Default")
      (node (ref "J14") (pin "28") (pinfunction "28_28") (pintype "passive"))
      (node (ref "J9") (pin "28") (pinfunction "28_28") (pintype "passive"))
    )
    (net (code "42") (name "/JGPIO 30") (class "Default")
      (node (ref "J14") (pin "30") (pinfunction "30_30") (pintype "passive"))
      (node (ref "J9") (pin "30") (pinfunction "30_30") (pintype "passive"))
    )
    (net (code "43") (name "/JGPIO 32") (class "Default")
      (node (ref "J14") (pin "32") (pinfunction "32_32") (pintype "passive"))
      (node (ref "J9") (pin "32") (pinfunction "32_32") (pintype "passive"))
    )
    (net (code "44") (name "/JGPIO 33") (class "Default")
      (node (ref "J14") (pin "33") (pinfunction "33_33") (pintype "passive"))
      (node (ref "J9") (pin "33") (pinfunction "33_33") (pintype "passive"))
    )
    (net (code "45") (name "/JGPIO 34") (class "Default")
      (node (ref "J14") (pin "34") (pinfunction "34_34") (pintype "passive"))
      (node (ref "J9") (pin "34") (pinfunction "34_34") (pintype "passive"))
    )
    (net (code "46") (name "/JGPIO 35") (class "Default")
      (node (ref "J14") (pin "35") (pinfunction "35_35") (pintype "passive"))
      (node (ref "J9") (pin "35") (pinfunction "35_35") (pintype "passive"))
    )
    (net (code "47") (name "/JGPIO 36") (class "Default")
      (node (ref "J14") (pin "36") (pinfunction "36_36") (pintype "passive"))
      (node (ref "J9") (pin "36") (pinfunction "36_36") (pintype "passive"))
    )
    (net (code "48") (name "/JGPIO 37") (class "Default")
      (node (ref "J14") (pin "37") (pinfunction "37_37") (pintype "passive"))
      (node (ref "J9") (pin "37") (pinfunction "37_37") (pintype "passive"))
    )
    (net (code "49") (name "/JGPIO 38") (class "Default")
      (node (ref "J14") (pin "38") (pinfunction "38_38") (pintype "passive"))
      (node (ref "J9") (pin "38") (pinfunction "38_38") (pintype "passive"))
    )
    (net (code "50") (name "/JGPIO 40") (class "Default")
      (node (ref "J14") (pin "40") (pinfunction "40_40") (pintype "passive"))
      (node (ref "J9") (pin "40") (pinfunction "40_40") (pintype "passive"))
    )
    (net (code "51") (name "/NRST") (class "Default")
      (node (ref "IC1") (pin "7") (pinfunction "NRST_7") (pintype "passive"))
      (node (ref "R5") (pin "1") (pinfunction "1_1") (pintype "passive"))
      (node (ref "SW1") (pin "2") (pinfunction "2_2") (pintype "passive"))
    )
    (net (code "52") (name "/PWM5V_1") (class "Default")
      (node (ref "J10") (pin "2") (pinfunction "2_2") (pintype "passive"))
      (node (ref "R31") (pin "2") (pinfunction "2_2") (pintype "passive"))
    )
    (net (code "53") (name "/PWM5V_2") (class "Default")
      (node (ref "J11") (pin "2") (pinfunction "2_2") (pintype "passive"))
      (node (ref "R32") (pin "2") (pinfunction "2_2") (pintype "passive"))
    )
    (net (code "54") (name "/PWM5V_3") (class "Default")
      (node (ref "J12") (pin "2") (pinfunction "2_2") (pintype "passive"))
      (node (ref "R33") (pin "2") (pinfunction "2_2") (pintype "passive"))
    )
    (net (code "55") (name "/PWM5V_4") (class "Default")
      (node (ref "J13") (pin "2") (pinfunction "2_2") (pintype "passive"))
      (node (ref "R34") (pin "2") (pinfunction "2_2") (pintype "passive"))
    )
    (net (code "56") (name "/REGPG1") (class "Default")
      (node (ref "C17") (pin "2") (pinfunction "2_2") (pintype "passive"))
      (node (ref "D3") (pin "2") (pinfunction "CH2_2") (pintype "passive"))
      (node (ref "D3") (pin "9") (pinfunction "N.C._3_9") (pintype "passive"))
      (node (ref "R4") (pin "2") (pinfunction "2_2") (pintype "passive"))
    )
    (net (code "57") (name "/REGPG2") (class "Default")
      (node (ref "C15") (pin "2") (pinfunction "2_2") (pintype "passive"))
      (node (ref "D3") (pin "5") (pinfunction "CH4_5") (pintype "passive"))
      (node (ref "D3") (pin "6") (pinfunction "N.C._1_6") (pintype "passive"))
      (node (ref "R6") (pin "2") (pinfunction "2_2") (pintype "passive"))
    )
    (net (code "58") (name "/REGPG3") (class "Default")
      (node (ref "C13") (pin "2") (pinfunction "2_2") (pintype "passive"))
      (node (ref "D2") (pin "2") (pinfunction "CH2_2") (pintype "passive"))
      (node (ref "D2") (pin "9") (pinfunction "N.C._3_9") (pintype "passive"))
      (node (ref "R8") (pin "2") (pinfunction "2_2") (pintype "passive"))
    )
    (net (code "59") (name "/REGPG4") (class "Default")
      (node (ref "C32") (pin "2") (pinfunction "2_2") (pintype "passive"))
      (node (ref "D2") (pin "5") (pinfunction "CH4_5") (pintype "passive"))
      (node (ref "D2") (pin "6") (pinfunction "N.C._1_6") (pintype "passive"))
      (node (ref "R16") (pin "1") (pinfunction "1_1") (pintype "passive"))
    )
    (net (code "60") (name "/REGPG5") (class "Default")
      (node (ref "C23") (pin "2") (pinfunction "2_2") (pintype "passive"))
      (node (ref "D5") (pin "1") (pinfunction "CH1_1") (pintype "passive"))
      (node (ref "D5") (pin "10") (pinfunction "N.C._4_10") (pintype "passive"))
      (node (ref "R22") (pin "1") (pinfunction "1_1") (pintype "passive"))
    )
    (net (code "61") (name "/REGPG6") (class "Default")
      (node (ref "C26") (pin "2") (pinfunction "2_2") (pintype "passive"))
      (node (ref "D6") (pin "5") (pinfunction "CH4_5") (pintype "passive"))
      (node (ref "D6") (pin "6") (pinfunction "N.C._1_6") (pintype "passive"))
      (node (ref "R12") (pin "1") (pinfunction "1_1") (pintype "passive"))
    )
    (net (code "62") (name "/REGPG7") (class "Default")
      (node (ref "C31") (pin "2") (pinfunction "2_2") (pintype "passive"))
      (node (ref "D6") (pin "1") (pinfunction "CH1_1") (pintype "passive"))
      (node (ref "D6") (pin "10") (pinfunction "N.C._4_10") (pintype "passive"))
      (node (ref "R15") (pin "1") (pinfunction "1_1") (pintype "passive"))
    )
    (net (code "63") (name "/SCL") (class "Default")
      (node (ref "C10") (pin "1") (pinfunction "1_1") (pintype "passive"))
      (node (ref "D1") (pin "5") (pinfunction "CH4_5") (pintype "passive"))
      (node (ref "D1") (pin "6") (pinfunction "N.C._1_6") (pintype "passive"))
      (node (ref "J1") (pin "6") (pinfunction "6_6") (pintype "passive"))
      (node (ref "J14") (pin "5") (pinfunction "5_5") (pintype "passive"))
      (node (ref "J5") (pin "2") (pinfunction "2_2") (pintype "passive"))
      (node (ref "J9") (pin "5") (pinfunction "5_5") (pintype "passive"))
      (node (ref "R2") (pin "1") (pinfunction "1_1") (pintype "passive"))
      (node (ref "R25") (pin "2") (pinfunction "2_2") (pintype "passive"))
    )
    (net (code "64") (name "/SDA") (class "Default")
      (node (ref "C9") (pin "1") (pinfunction "1_1") (pintype "passive"))
      (node (ref "D1") (pin "4") (pinfunction "CH3_4") (pintype "passive"))
      (node (ref "D1") (pin "7") (pinfunction "N.C._2_7") (pintype "passive"))
      (node (ref "J1") (pin "5") (pinfunction "5_5") (pintype "passive"))
      (node (ref "J14") (pin "3") (pinfunction "3_3") (pintype "passive"))
      (node (ref "J5") (pin "1") (pinfunction "1_1") (pintype "passive"))
      (node (ref "J9") (pin "3") (pinfunction "3_3") (pintype "passive"))
      (node (ref "R1") (pin "2") (pinfunction "2_2") (pintype "passive"))
      (node (ref "R11") (pin "2") (pinfunction "2_2") (pintype "passive"))
    )
    (net (code "65") (name "/SWDCK") (class "Default")
      (node (ref "IC1") (pin "37") (pinfunction "PA14_37") (pintype "passive"))
      (node (ref "J4") (pin "2") (pinfunction "2_2") (pintype "passive"))
    )
    (net (code "66") (name "/SWDIO") (class "Default")
      (node (ref "IC1") (pin "34") (pinfunction "PA13_34") (pintype "passive"))
      (node (ref "J4") (pin "1") (pinfunction "1_1") (pintype "passive"))
    )
    (net (code "67") (name "/TOGGLE1") (class "Default")
      (node (ref "C18") (pin "2") (pinfunction "2_2") (pintype "passive"))
      (node (ref "D3") (pin "1") (pinfunction "CH1_1") (pintype "passive"))
      (node (ref "D3") (pin "10") (pinfunction "N.C._4_10") (pintype "passive"))
      (node (ref "R19") (pin "2") (pinfunction "2_2") (pintype "passive"))
    )
    (net (code "68") (name "/TOGGLE2") (class "Default")
      (node (ref "C16") (pin "2") (pinfunction "2_2") (pintype "passive"))
      (node (ref "D3") (pin "4") (pinfunction "CH3_4") (pintype "passive"))
      (node (ref "D3") (pin "7") (pinfunction "N.C._2_7") (pintype "passive"))
      (node (ref "R20") (pin "2") (pinfunction "2_2") (pintype "passive"))
    )
    (net (code "69") (name "/TOGGLE3") (class "Default")
      (node (ref "C14") (pin "2") (pinfunction "2_2") (pintype "passive"))
      (node (ref "D2") (pin "1") (pinfunction "CH1_1") (pintype "passive"))
      (node (ref "D2") (pin "10") (pinfunction "N.C._4_10") (pintype "passive"))
      (node (ref "R7") (pin "2") (pinfunction "2_2") (pintype "passive"))
    )
    (net (code "70") (name "/TOGGLE4") (class "Default")
      (node (ref "C33") (pin "2") (pinfunction "2_2") (pintype "passive"))
      (node (ref "D2") (pin "4") (pinfunction "CH3_4") (pintype "passive"))
      (node (ref "D2") (pin "7") (pinfunction "N.C._2_7") (pintype "passive"))
      (node (ref "R23") (pin "1") (pinfunction "1_1") (pintype "passive"))
    )
    (net (code "71") (name "/TOGGLE5") (class "Default")
      (node (ref "C22") (pin "2") (pinfunction "2_2") (pintype "passive"))
      (node (ref "D5") (pin "2") (pinfunction "CH2_2") (pintype "passive"))
      (node (ref "D5") (pin "9") (pinfunction "N.C._3_9") (pintype "passive"))
      (node (ref "R21") (pin "1") (pinfunction "1_1") (pintype "passive"))
    )
    (net (code "72") (name "/TOGGLE6") (class "Default")
      (node (ref "C27") (pin "2") (pinfunction "2_2") (pintype "passive"))
      (node (ref "D6") (pin "4") (pinfunction "CH3_4") (pintype "passive"))
      (node (ref "D6") (pin "7") (pinfunction "N.C._2_7") (pintype "passive"))
      (node (ref "R13") (pin "1") (pinfunction "1_1") (pintype "passive"))
    )
    (net (code "73") (name "/TOGGLE7") (class "Default")
      (node (ref "C30") (pin "2") (pinfunction "2_2") (pintype "passive"))
      (node (ref "D6") (pin "2") (pinfunction "CH2_2") (pintype "passive"))
      (node (ref "D6") (pin "9") (pinfunction "N.C._3_9") (pintype "passive"))
      (node (ref "R14") (pin "1") (pinfunction "1_1") (pintype "passive"))
    )
    (net (code "74") (name "/{slash}Enable") (class "Default")
      (node (ref "IC3") (pin "1") (pinfunction "~{1OE}_1") (pintype "passive"))
      (node (ref "R24") (pin "2") (pinfunction "2_2") (pintype "passive"))
    )
    (net (code "75") (name "/{slash}Enable2") (class "Default")
      (node (ref "IC3") (pin "19") (pinfunction "~{2OE}_19") (pintype "passive"))
      (node (ref "R26") (pin "2") (pinfunction "2_2") (pintype "passive"))
    )
    (net (code "76") (name "GND") (class "Default")
      (node (ref "AUX") (pin "3") (pinfunction "3_3") (pintype "passive"))
      (node (ref "BIG_BUCK") (pin "10") (pinfunction "VIN(-)_10") (pintype "input"))
      (node (ref "BIG_BUCK") (pin "2") (pinfunction "~{ON/OFF}_2") (pintype "input"))
      (node (ref "BIG_BUCK") (pin "3") (pinfunction "VIN(-)/GND_3") (pintype "input"))
      (node (ref "BIG_BUCK") (pin "4") (pinfunction "VOUT(-)/GND_4") (pintype "output"))
      (node (ref "C1") (pin "2") (pinfunction "2_2") (pintype "passive"))
      (node (ref "C10") (pin "2") (pinfunction "2_2") (pintype "passive"))
      (node (ref "C13") (pin "1") (pinfunction "1_1") (pintype "passive"))
      (node (ref "C14") (pin "1") (pinfunction "1_1") (pintype "passive"))
      (node (ref "C15") (pin "1") (pinfunction "1_1") (pintype "passive"))
      (node (ref "C16") (pin "1") (pinfunction "1_1") (pintype "passive"))
      (node (ref "C17") (pin "1") (pinfunction "1_1") (pintype "passive"))
      (node (ref "C18") (pin "1") (pinfunction "1_1") (pintype "passive"))
      (node (ref "C2") (pin "2") (pinfunction "2_2") (pintype "passive"))
      (node (ref "C22") (pin "1") (pinfunction "1_1") (pintype "passive"))
      (node (ref "C23") (pin "1") (pinfunction "1_1") (pintype "passive"))
      (node (ref "C24") (pin "2") (pinfunction "2_2") (pintype "passive"))
      (node (ref "C25") (pin "2") (pinfunction "2_2") (pintype "passive"))
      (node (ref "C26") (pin "1") (pinfunction "1_1") (pintype "passive"))
      (node (ref "C27") (pin "1") (pinfunction "1_1") (pintype "passive"))
      (node (ref "C28") (pin "1") (pinfunction "1_1") (pintype "passive"))
      (node (ref "C29") (pin "1") (pinfunction "1_1") (pintype "passive"))
      (node (ref "C3") (pin "2") (pinfunction "2_2") (pintype "passive"))
      (node (ref "C30") (pin "1") (pinfunction "1_1") (pintype "passive"))
      (node (ref "C31") (pin "1") (pinfunction "1_1") (pintype "passive"))
      (node (ref "C32") (pin "1") (pinfunction "1_1") (pintype "passive"))
      (node (ref "C33") (pin "1") (pinfunction "1_1") (pintype "passive"))
      (node (ref "C34") (pin "2") (pinfunction "2_2") (pintype "passive"))
      (node (ref "C35") (pin "1") (pinfunction "1_1") (pintype "passive"))
      (node (ref "C4") (pin "2") (pinfunction "2_2") (pintype "passive"))
      (node (ref "C5") (pin "2") (pinfunction "2_2") (pintype "passive"))
      (node (ref "C6") (pin "2") (pinfunction "2_2") (pintype "passive"))
      (node (ref "C7") (pin "2") (pinfunction "2_2") (pintype "passive"))
      (node (ref "C8") (pin "2") (pinfunction "2_2") (pintype "passive"))
      (node (ref "C9") (pin "2") (pinfunction "2_2") (pintype "passive"))
      (node (ref "CAN_OUT") (pin "4") (pinfunction "4_4") (pintype "passive"))
      (node (ref "D1") (pin "3") (pinfunction "GND_1_3") (pintype "passive"))
      (node (ref "D1") (pin "8") (pinfunction "GND_2_8") (pintype "passive"))
      (node (ref "D2") (pin "3") (pinfunction "GND_1_3") (pintype "passive"))
      (node (ref "D2") (pin "8") (pinfunction "GND_2_8") (pintype "passive"))
      (node (ref "D3") (pin "3") (pinfunction "GND_1_3") (pintype "passive"))
      (node (ref "D3") (pin "8") (pinfunction "GND_2_8") (pintype "passive"))
      (node (ref "D5") (pin "3") (pinfunction "GND_1_3") (pintype "passive"))
      (node (ref "D5") (pin "8") (pinfunction "GND_2_8") (pintype "passive"))
      (node (ref "D6") (pin "3") (pinfunction "GND_1_3") (pintype "passive"))
      (node (ref "D6") (pin "8") (pinfunction "GND_2_8") (pintype "passive"))
      (node (ref "IC1") (pin "23") (pinfunction "VSS_1_23") (pintype "passive"))
      (node (ref "IC1") (pin "35") (pinfunction "VSS_2_35") (pintype "passive"))
      (node (ref "IC1") (pin "47") (pinfunction "VSS_3_47") (pintype "passive"))
      (node (ref "IC1") (pin "8") (pinfunction "VSSA_8") (pintype "passive"))
      (node (ref "IC2") (pin "1") (pinfunction "ADJ/GND_1") (pintype "passive"))
      (node (ref "IC3") (pin "10") (pinfunction "GND_10") (pintype "passive"))
      (node (ref "J10") (pin "3") (pinfunction "3_3") (pintype "passive"))
      (node (ref "J11") (pin "3") (pinfunction "3_3") (pintype "passive"))
      (node (ref "J12") (pin "3") (pinfunction "3_3") (pintype "passive"))
      (node (ref "J13") (pin "3") (pinfunction "3_3") (pintype "passive"))
      (node (ref "J14") (pin "39") (pinfunction "39_39") (pintype "passive"))
      (node (ref "J16") (pin "2") (pinfunction "2_2") (pintype "passive"))
      (node (ref "J16") (pin "3") (pinfunction "3_3") (pintype "passive"))
      (node (ref "J2") (pin "1") (pinfunction "1_1") (pintype "passive"))
      (node (ref "J2") (pin "2") (pinfunction "2_2") (pintype "passive"))
      (node (ref "J2") (pin "3") (pinfunction "3_3") (pintype "passive"))
      (node (ref "J2") (pin "4") (pinfunction "4_4") (pintype "passive"))
      (node (ref "J6") (pin "1") (pinfunction "1_1") (pintype "passive"))
      (node (ref "J6") (pin "2") (pinfunction "2_2") (pintype "passive"))
      (node (ref "J7") (pin "3") (pinfunction "3_3") (pintype "passive"))
      (node (ref "J7") (pin "4") (pinfunction "4_4") (pintype "passive"))
      (node (ref "J8") (pin "3") (pinfunction "3_3") (pintype "passive"))
      (node (ref "J8") (pin "4") (pinfunction "4_4") (pintype "passive"))
      (node (ref "J9") (pin "39") (pinfunction "39_39") (pintype "passive"))
      (node (ref "LED1") (pin "1") (pinfunction "1_1") (pintype "passive"))
      (node (ref "LED2") (pin "1") (pinfunction "1_1") (pintype "passive"))
      (node (ref "LED3") (pin "1") (pinfunction "1_1") (pintype "passive"))
      (node (ref "LED4") (pin "1") (pinfunction "1_1") (pintype "passive"))
      (node (ref "LED5") (pin "1") (pinfunction "1_1") (pintype "passive"))
      (node (ref "LED6") (pin "1") (pinfunction "1_1") (pintype "passive"))
      (node (ref "PS1") (pin "3") (pinfunction "GND_(COMMON)_3") (pintype "passive"))
      (node (ref "R17") (pin "1") (pinfunction "1_1") (pintype "passive"))
      (node (ref "R18") (pin "1") (pinfunction "1_1") (pintype "passive"))
      (node (ref "R24") (pin "1") (pinfunction "1_1") (pintype "passive"))
      (node (ref "R27") (pin "2") (pinfunction "2_2") (pintype "passive"))
      (node (ref "R28") (pin "2") (pinfunction "2_2") (pintype "passive"))
      (node (ref "R29") (pin "2") (pinfunction "2_2") (pintype "passive"))
      (node (ref "R3") (pin "2") (pinfunction "2_2") (pintype "passive"))
      (node (ref "R30") (pin "2") (pinfunction "2_2") (pintype "passive"))
      (node (ref "R44") (pin "2") (pinfunction "2_2") (pintype "passive"))
      (node (ref "SW1") (pin "1") (pinfunction "1_1") (pintype "passive"))
    )
    (net (code "77") (name "Net-(BIG_BUCK-TRIM)") (class "Default")
      (node (ref "BIG_BUCK") (pin "6") (pinfunction "TRIM_6") (pintype "passive"))
      (node (ref "R17") (pin "2") (pinfunction "2_2") (pintype "passive"))
    )
    (net (code "78") (name "Net-(F1-Pad2)") (class "Default")
      (node (ref "F1") (pin "2") (pinfunction "2_2") (pintype "passive"))
      (node (ref "J8") (pin "1") (pinfunction "1_1") (pintype "passive"))
      (node (ref "J8") (pin "2") (pinfunction "2_2") (pintype "passive"))
      (node (ref "R9") (pin "2") (pinfunction "2_2") (pintype "passive"))
    )
    (net (code "79") (name "Net-(F2-Pad2)") (class "Default")
      (node (ref "F2") (pin "2") (pinfunction "2_2") (pintype "passive"))
      (node (ref "J7") (pin "1") (pinfunction "1_1") (pintype "passive"))
      (node (ref "J7") (pin "2") (pinfunction "2_2") (pintype "passive"))
      (node (ref "R10") (pin "2") (pinfunction "2_2") (pintype "passive"))
    )
    (net (code "80") (name "Net-(F4-Pad1)") (class "Default")
      (node (ref "F4") (pin "1") (pinfunction "1_1") (pintype "passive"))
      (node (ref "J16") (pin "6") (pinfunction "6_6") (pintype "passive"))
      (node (ref "R36") (pin "2") (pinfunction "2_2") (pintype "passive"))
    )
    (net (code "81") (name "Net-(F5-Pad1)") (class "Default")
      (node (ref "F5") (pin "1") (pinfunction "1_1") (pintype "passive"))
      (node (ref "J16") (pin "5") (pinfunction "5_5") (pintype "passive"))
      (node (ref "R35") (pin "2") (pinfunction "2_2") (pintype "passive"))
    )
    (net (code "82") (name "Net-(F6-Pad1)") (class "Default")
      (node (ref "F6") (pin "1") (pinfunction "1_1") (pintype "passive"))
      (node (ref "J2") (pin "5") (pinfunction "5_5") (pintype "passive"))
      (node (ref "J2") (pin "6") (pinfunction "6_6") (pintype "passive"))
      (node (ref "J2") (pin "7") (pinfunction "7_7") (pintype "passive"))
      (node (ref "J2") (pin "8") (pinfunction "8_8") (pintype "passive"))
      (node (ref "R37") (pin "2") (pinfunction "2_2") (pintype "passive"))
    )
    (net (code "83") (name "Net-(F7-Pad1)") (class "Default")
      (node (ref "F7") (pin "1") (pinfunction "1_1") (pintype "passive"))
      (node (ref "J5") (pin "3") (pinfunction "3_3") (pintype "passive"))
      (node (ref "R38") (pin "2") (pinfunction "2_2") (pintype "passive"))
    )
    (net (code "84") (name "Net-(IC1-BOOT0)") (class "Default")
      (node (ref "IC1") (pin "44") (pinfunction "BOOT0_44") (pintype "passive"))
      (node (ref "R3") (pin "1") (pinfunction "1_1") (pintype "passive"))
    )
    (net (code "85") (name "Net-(IC1-PA4)") (class "Default")
      (node (ref "IC1") (pin "14") (pinfunction "PA4_14") (pintype "passive"))
      (node (ref "R21") (pin "2") (pinfunction "2_2") (pintype "passive"))
    )
    (net (code "86") (name "Net-(IC1-PA5)") (class "Default")
      (node (ref "IC1") (pin "15") (pinfunction "PA5_15") (pintype "passive"))
      (node (ref "R22") (pin "2") (pinfunction "2_2") (pintype "passive"))
    )
    (net (code "87") (name "Net-(IC1-PA6)") (class "Default")
      (node (ref "IC1") (pin "16") (pinfunction "PA6_16") (pintype "passive"))
      (node (ref "R12") (pin "2") (pinfunction "2_2") (pintype "passive"))
    )
    (net (code "88") (name "Net-(IC1-PA7)") (class "Default")
      (node (ref "IC1") (pin "17") (pinfunction "PA7_17") (pintype "passive"))
      (node (ref "R13") (pin "2") (pinfunction "2_2") (pintype "passive"))
    )
    (net (code "89") (name "Net-(IC1-PA8)") (class "Default")
      (node (ref "IC1") (pin "29") (pinfunction "PA8_29") (pintype "passive"))
      (node (ref "R20") (pin "1") (pinfunction "1_1") (pintype "passive"))
    )
    (net (code "90") (name "Net-(IC1-PA9)") (class "Default")
      (node (ref "IC1") (pin "30") (pinfunction "PA9_30") (pintype "passive"))
      (node (ref "R4") (pin "1") (pinfunction "1_1") (pintype "passive"))
    )
    (net (code "91") (name "Net-(IC1-PA10)") (class "Default")
      (node (ref "IC1") (pin "31") (pinfunction "PA10_31") (pintype "passive"))
      (node (ref "R19") (pin "1") (pinfunction "1_1") (pintype "passive"))
    )
    (net (code "92") (name "Net-(IC1-PB0)") (class "Default")
      (node (ref "IC1") (pin "18") (pinfunction "PB0_18") (pintype "passive"))
      (node (ref "R14") (pin "2") (pinfunction "2_2") (pintype "passive"))
    )
    (net (code "93") (name "Net-(IC1-PB1)") (class "Default")
      (node (ref "IC1") (pin "19") (pinfunction "PB1_19") (pintype "passive"))
      (node (ref "R15") (pin "2") (pinfunction "2_2") (pintype "passive"))
    )
    (net (code "94") (name "Net-(IC1-PB2)") (class "Default")
      (node (ref "IC1") (pin "20") (pinfunction "PB2_20") (pintype "passive"))
      (node (ref "R18") (pin "2") (pinfunction "2_2") (pintype "passive"))
    )
    (net (code "95") (name "Net-(IC1-PB6)") (class "Default")
      (node (ref "IC1") (pin "42") (pinfunction "PB6_42") (pintype "passive"))
      (node (ref "R25") (pin "1") (pinfunction "1_1") (pintype "passive"))
    )
    (net (code "96") (name "Net-(IC1-PB7)") (class "Default")
      (node (ref "IC1") (pin "43") (pinfunction "PB7_43") (pintype "passive"))
      (node (ref "R11") (pin "1") (pinfunction "1_1") (pintype "passive"))
    )
    (net (code "97") (name "Net-(IC1-PB10)") (class "Default")
      (node (ref "IC1") (pin "21") (pinfunction "PB10_21") (pintype "passive"))
      (node (ref "R16") (pin "2") (pinfunction "2_2") (pintype "passive"))
    )
    (net (code "98") (name "Net-(IC1-PB11)") (class "Default")
      (node (ref "IC1") (pin "22") (pinfunction "PB11_22") (pintype "passive"))
      (node (ref "R23") (pin "2") (pinfunction "2_2") (pintype "passive"))
    )
    (net (code "99") (name "Net-(IC1-PB13)") (class "Default")
      (node (ref "IC1") (pin "26") (pinfunction "PB13_26") (pintype "passive"))
      (node (ref "R8") (pin "1") (pinfunction "1_1") (pintype "passive"))
    )
    (net (code "100") (name "Net-(IC1-PB14)") (class "Default")
      (node (ref "IC1") (pin "27") (pinfunction "PB14_27") (pintype "passive"))
      (node (ref "R7") (pin "1") (pinfunction "1_1") (pintype "passive"))
    )
    (net (code "101") (name "Net-(IC1-PB15)") (class "Default")
      (node (ref "IC1") (pin "28") (pinfunction "PB15_28") (pintype "passive"))
      (node (ref "R6") (pin "1") (pinfunction "1_1") (pintype "passive"))
    )
    (net (code "102") (name "Net-(LED1-Pad2)") (class "Default")
      (node (ref "LED1") (pin "2") (pinfunction "2_2") (pintype "passive"))
      (node (ref "R9") (pin "1") (pinfunction "1_1") (pintype "passive"))
    )
    (net (code "103") (name "Net-(LED2-Pad2)") (class "Default")
      (node (ref "LED2") (pin "2") (pinfunction "2_2") (pintype "passive"))
      (node (ref "R10") (pin "1") (pinfunction "1_1") (pintype "passive"))
    )
    (net (code "104") (name "Net-(LED3-Pad2)") (class "Default")
      (node (ref "LED3") (pin "2") (pinfunction "2_2") (pintype "passive"))
      (node (ref "R35") (pin "1") (pinfunction "1_1") (pintype "passive"))
    )
    (net (code "105") (name "Net-(LED4-Pad2)") (class "Default")
      (node (ref "LED4") (pin "2") (pinfunction "2_2") (pintype "passive"))
      (node (ref "R36") (pin "1") (pinfunction "1_1") (pintype "passive"))
    )
    (net (code "106") (name "Net-(LED5-Pad2)") (class "Default")
      (node (ref "LED5") (pin "2") (pinfunction "2_2") (pintype "passive"))
      (node (ref "R37") (pin "1") (pinfunction "1_1") (pintype "passive"))
    )
    (net (code "107") (name "Net-(LED6-Pad2)") (class "Default")
      (node (ref "LED6") (pin "2") (pinfunction "2_2") (pintype "passive"))
      (node (ref "R38") (pin "1") (pinfunction "1_1") (pintype "passive"))
    )
    (net (code "108") (name "Net-(PS1-REMOTE_ON{slash}OFF)") (class "Default")
      (node (ref "PS1") (pin "5") (pinfunction "REMOTE_ON/OFF_5") (pintype "passive"))
      (node (ref "R43") (pin "2") (pinfunction "2_2") (pintype "passive"))
      (node (ref "R44") (pin "1") (pinfunction "1_1") (pintype "passive"))
    )
    (net (code "109") (name "VBAT+") (class "Default")
      (node (ref "BIG_BUCK") (pin "1") (pinfunction "VIN(+)_1") (pintype "input"))
      (node (ref "BIG_BUCK") (pin "9") (pinfunction "VIN(+)_9") (pintype "input"))
      (node (ref "C24") (pin "1") (pinfunction "1_1") (pintype "passive"))
      (node (ref "C28") (pin "2") (pinfunction "2_2") (pintype "passive"))
      (node (ref "F1") (pin "1") (pinfunction "1_1") (pintype "passive"))
      (node (ref "F6") (pin "2") (pinfunction "2_2") (pintype "passive"))
    )
    (net (code "110") (name "unconnected-(D1-CH1-Pad1)") (class "Default")
      (node (ref "D1") (pin "1") (pinfunction "CH1_1") (pintype "passive"))
    )
    (net (code "111") (name "unconnected-(D1-CH2-Pad2)") (class "Default")
      (node (ref "D1") (pin "2") (pinfunction "CH2_2") (pintype "passive"))
    )
    (net (code "112") (name "unconnected-(D1-N.C._3-Pad9)") (class "Default")
      (node (ref "D1") (pin "9") (pinfunction "N.C._3_9") (pintype "passive"))
    )
    (net (code "113") (name "unconnected-(D1-N.C._4-Pad10)") (class "Default")
      (node (ref "D1") (pin "10") (pinfunction "N.C._4_10") (pintype "passive"))
    )
    (net (code "114") (name "unconnected-(D5-CH3-Pad4)") (class "Default")
      (node (ref "D5") (pin "4") (pinfunction "CH3_4") (pintype "passive+no_connect"))
    )
    (net (code "115") (name "unconnected-(D5-CH4-Pad5)") (class "Default")
      (node (ref "D5") (pin "5") (pinfunction "CH4_5") (pintype "passive+no_connect"))
    )
    (net (code "116") (name "unconnected-(D5-N.C._1-Pad6)") (class "Default")
      (node (ref "D5") (pin "6") (pinfunction "N.C._1_6") (pintype "passive+no_connect"))
    )
    (net (code "117") (name "unconnected-(D5-N.C._2-Pad7)") (class "Default")
      (node (ref "D5") (pin "7") (pinfunction "N.C._2_7") (pintype "passive+no_connect"))
    )
    (net (code "118") (name "unconnected-(IC1-PA0-WKUP-Pad10)") (class "Default")
      (node (ref "IC1") (pin "10") (pinfunction "PA0-WKUP_10") (pintype "passive+no_connect"))
    )
    (net (code "119") (name "unconnected-(IC1-PA1-Pad11)") (class "Default")
      (node (ref "IC1") (pin "11") (pinfunction "PA1_11") (pintype "passive+no_connect"))
    )
    (net (code "120") (name "unconnected-(IC1-PA2-Pad12)") (class "Default")
      (node (ref "IC1") (pin "12") (pinfunction "PA2_12") (pintype "passive+no_connect"))
    )
    (net (code "121") (name "unconnected-(IC1-PA3-Pad13)") (class "Default")
      (node (ref "IC1") (pin "13") (pinfunction "PA3_13") (pintype "passive+no_connect"))
    )
    (net (code "122") (name "unconnected-(IC1-PA11-Pad32)") (class "Default")
      (node (ref "IC1") (pin "32") (pinfunction "PA11_32") (pintype "passive+no_connect"))
    )
    (net (code "123") (name "unconnected-(IC1-PA12-Pad33)") (class "Default")
      (node (ref "IC1") (pin "33") (pinfunction "PA12_33") (pintype "passive+no_connect"))
    )
    (net (code "124") (name "unconnected-(IC1-PB8-Pad45)") (class "Default")
      (node (ref "IC1") (pin "45") (pinfunction "PB8_45") (pintype "passive"))
    )
    (net (code "125") (name "unconnected-(IC1-PB9-Pad46)") (class "Default")
      (node (ref "IC1") (pin "46") (pinfunction "PB9_46") (pintype "passive"))
    )
    (net (code "126") (name "unconnected-(IC1-PB12-Pad25)") (class "Default")
      (node (ref "IC1") (pin "25") (pinfunction "PB12_25") (pintype "passive+no_connect"))
    )
    (net (code "127") (name "unconnected-(IC1-PC13-TAMPER-RT_C-Pad2)") (class "Default")
      (node (ref "IC1") (pin "2") (pinfunction "PC13-TAMPER-RT_C_2") (pintype "passive+no_connect"))
    )
    (net (code "128") (name "unconnected-(IC1-PC14-OSC32_IN-Pad3)") (class "Default")
      (node (ref "IC1") (pin "3") (pinfunction "PC14-OSC32_IN_3") (pintype "passive+no_connect"))
    )
    (net (code "129") (name "unconnected-(IC1-PC15-OSC32_OUT-Pad4)") (class "Default")
      (node (ref "IC1") (pin "4") (pinfunction "PC15-OSC32_OUT_4") (pintype "passive+no_connect"))
    )
    (net (code "130") (name "unconnected-(IC1-PD0-OSC_IN-Pad5)") (class "Default")
      (node (ref "IC1") (pin "5") (pinfunction "PD0-OSC_IN_5") (pintype "passive+no_connect"))
    )
    (net (code "131") (name "unconnected-(IC1-PD1-OSC_OUT-Pad6)") (class "Default")
      (node (ref "IC1") (pin "6") (pinfunction "PD1-OSC_OUT_6") (pintype "passive+no_connect"))
    )
    (net (code "132") (name "unconnected-(IC3-2A0-Pad17)") (class "Default")
      (node (ref "IC3") (pin "17") (pinfunction "2A0_17") (pintype "passive+no_connect"))
    )
    (net (code "133") (name "unconnected-(IC3-2A1-Pad15)") (class "Default")
      (node (ref "IC3") (pin "15") (pinfunction "2A1_15") (pintype "passive+no_connect"))
    )
    (net (code "134") (name "unconnected-(IC3-2A2-Pad13)") (class "Default")
      (node (ref "IC3") (pin "13") (pinfunction "2A2_13") (pintype "passive+no_connect"))
    )
    (net (code "135") (name "unconnected-(IC3-2A3-Pad11)") (class "Default")
      (node (ref "IC3") (pin "11") (pinfunction "2A3_11") (pintype "passive+no_connect"))
    )
    (net (code "136") (name "unconnected-(IC3-2Y0-Pad3)") (class "Default")
      (node (ref "IC3") (pin "3") (pinfunction "2Y0_3") (pintype "passive+no_connect"))
    )
    (net (code "137") (name "unconnected-(IC3-2Y1-Pad5)") (class "Default")
      (node (ref "IC3") (pin "5") (pinfunction "2Y1_5") (pintype "passive+no_connect"))
    )
    (net (code "138") (name "unconnected-(IC3-2Y2-Pad7)") (class "Default")
      (node (ref "IC3") (pin "7") (pinfunction "2Y2_7") (pintype "passive+no_connect"))
    )
    (net (code "139") (name "unconnected-(IC3-2Y3-Pad9)") (class "Default")
      (node (ref "IC3") (pin "9") (pinfunction "2Y3_9") (pintype "passive+no_connect"))
    )
    (net (code "140") (name "unconnected-(J1-Pad3)") (class "Default")
      (node (ref "J1") (pin "3") (pinfunction "3_3") (pintype "passive+no_connect"))
    )
    (net (code "141") (name "unconnected-(J1-Pad4)") (class "Default")
      (node (ref "J1") (pin "4") (pinfunction "4_4") (pintype "passive+no_connect"))
    )
    (net (code "142") (name "unconnected-(J1-Pad7)") (class "Default")
      (node (ref "J1") (pin "7") (pinfunction "7_7") (pintype "passive+no_connect"))
    )
    (net (code "143") (name "unconnected-(J1-Pad8)") (class "Default")
      (node (ref "J1") (pin "8") (pinfunction "8_8") (pintype "passive+no_connect"))
    )
    (net (code "144") (name "unconnected-(J7-PadMH1)") (class "Default")
      (node (ref "J7") (pin "MH1") (pinfunction "MH1_MH1") (pintype "passive+no_connect"))
    )
    (net (code "145") (name "unconnected-(J7-PadMH2)") (class "Default")
      (node (ref "J7") (pin "MH2") (pinfunction "MH2_MH2") (pintype "passive+no_connect"))
    )
    (net (code "146") (name "unconnected-(J8-PadMH1)") (class "Default")
      (node (ref "J8") (pin "MH1") (pinfunction "MH1_MH1") (pintype "passive+no_connect"))
    )
    (net (code "147") (name "unconnected-(J8-PadMH2)") (class "Default")
      (node (ref "J8") (pin "MH2") (pinfunction "MH2_MH2") (pintype "passive+no_connect"))
    )
    (net (code "148") (name "unconnected-(J17-Pad1)") (class "Default")
      (node (ref "J17") (pin "1") (pinfunction "1_1") (pintype "passive+no_connect"))
    )
    (net (code "149") (name "unconnected-(J17-Pad2)") (class "Default")
      (node (ref "J17") (pin "2") (pinfunction "2_2") (pintype "passive+no_connect"))
    )
    (net (code "150") (name "unconnected-(J17-Pad3)") (class "Default")
      (node (ref "J17") (pin "3") (pinfunction "3_3") (pintype "passive+no_connect"))
    )
    (net (code "151") (name "unconnected-(J17-Pad4)") (class "Default")
      (node (ref "J17") (pin "4") (pinfunction "4_4") (pintype "passive+no_connect"))
    )
    (net (code "152") (name "unconnected-(J17-Pad5)") (class "Default")
      (node (ref "J17") (pin "5") (pinfunction "5_5") (pintype "passive+no_connect"))
    )
    (net (code "153") (name "unconnected-(J17-Pad6)") (class "Default")
      (node (ref "J17") (pin "6") (pinfunction "6_6") (pintype "passive+no_connect"))
    )
    (net (code "154") (name "unconnected-(J17-Pad7)") (class "Default")
      (node (ref "J17") (pin "7") (pinfunction "7_7") (pintype "passive+no_connect"))
    )
    (net (code "155") (name "unconnected-(J17-Pad8)") (class "Default")
      (node (ref "J17") (pin "8") (pinfunction "8_8") (pintype "passive+no_connect"))
    )
    (net (code "156") (name "unconnected-(PS1-TRIM-Pad2)") (class "Default")
      (node (ref "PS1") (pin "2") (pinfunction "TRIM_2") (pintype "passive"))
    )
  )
)
